# efi-shield.net
KiCad netlist of a schematic drawn in EAGLE
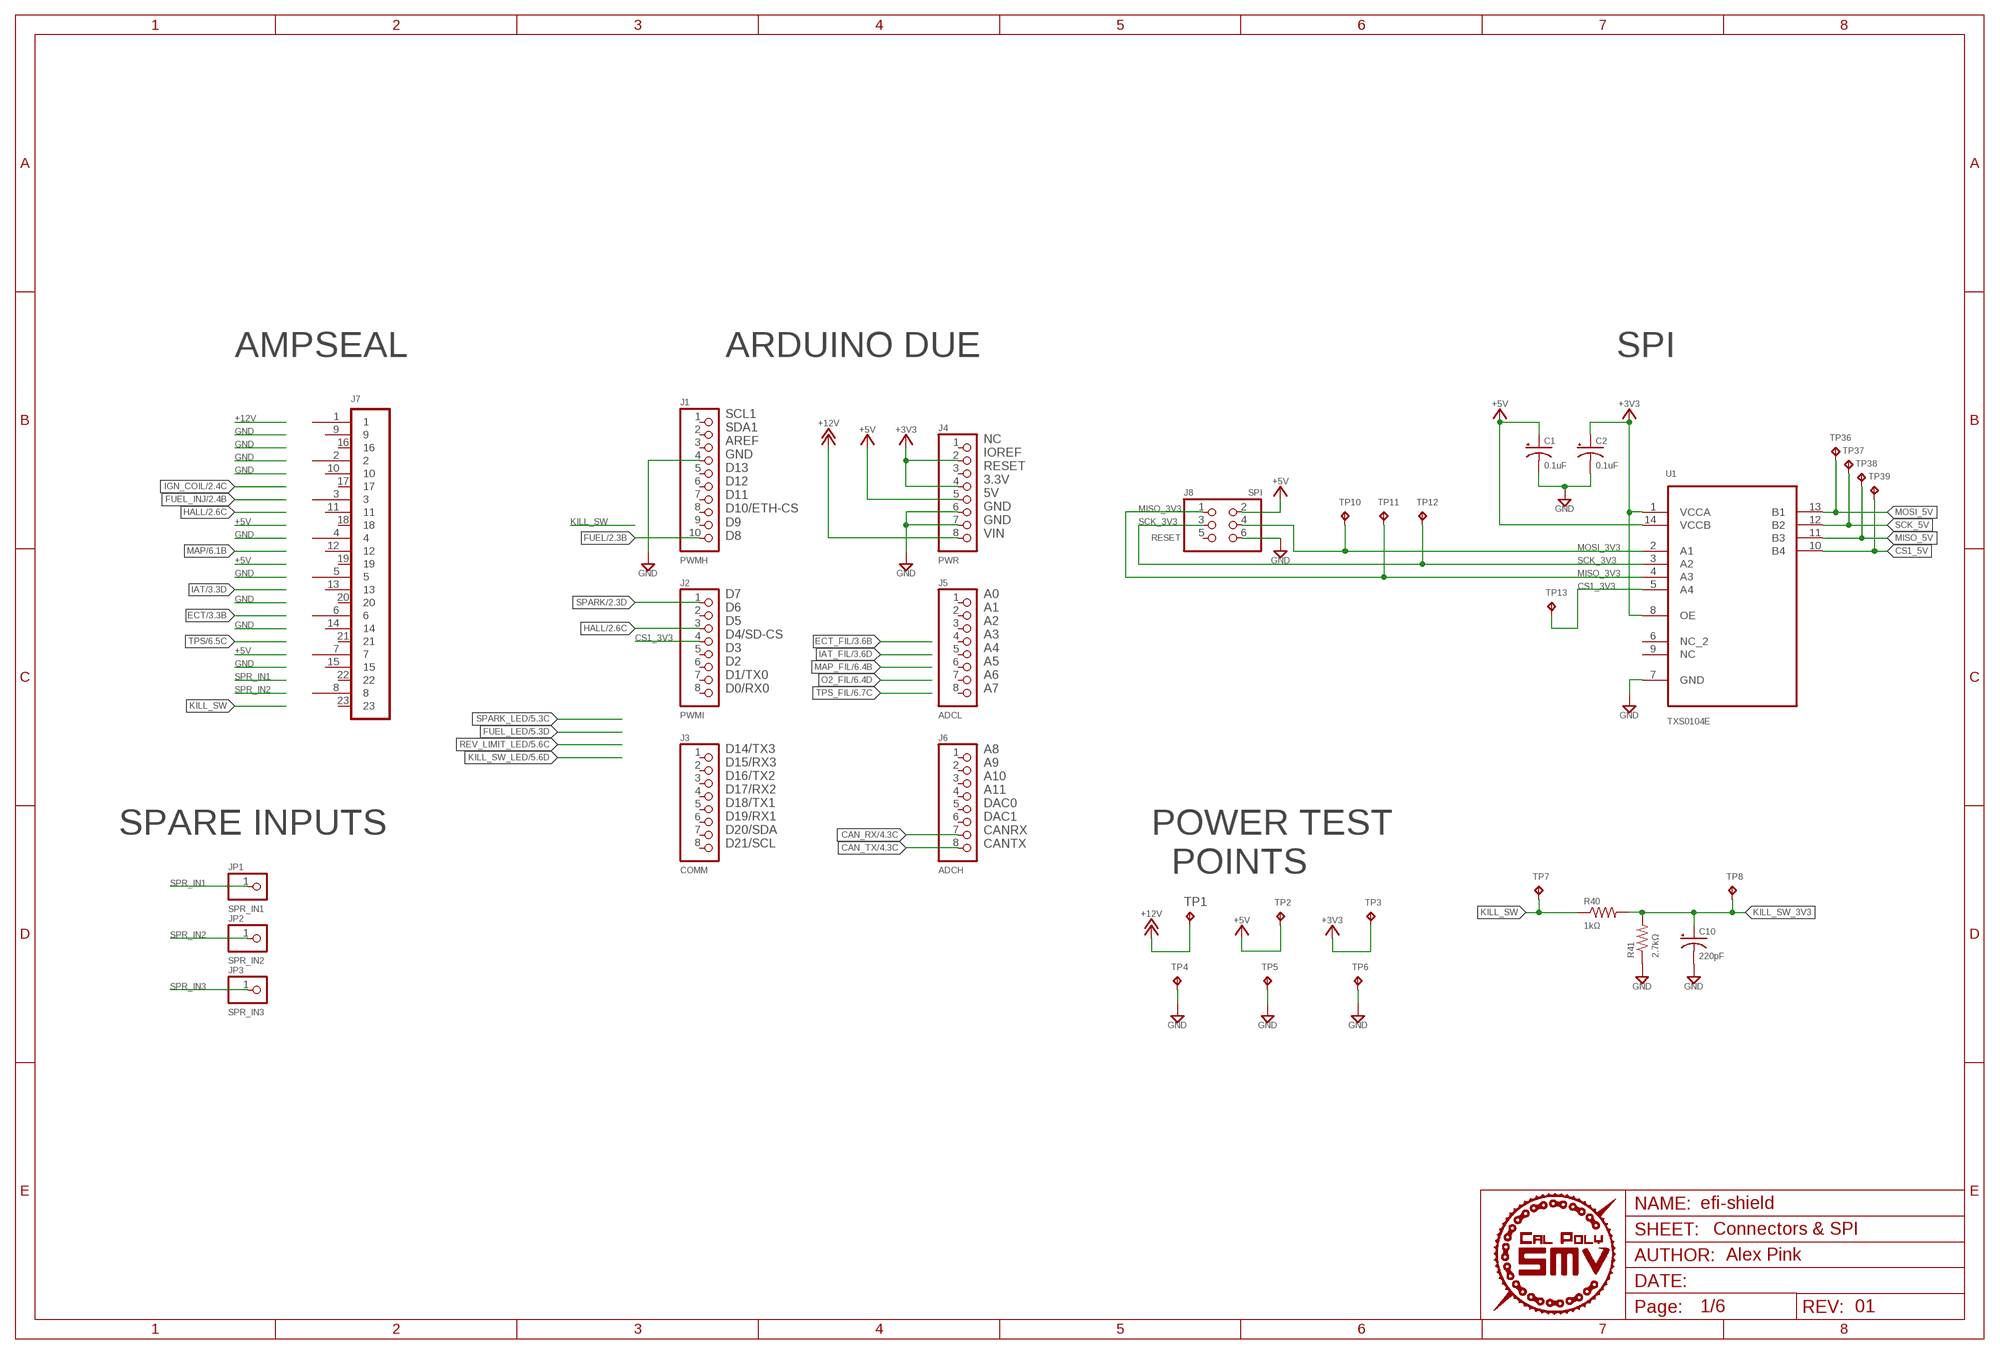
[diagram p0: schematic, sheet 1]
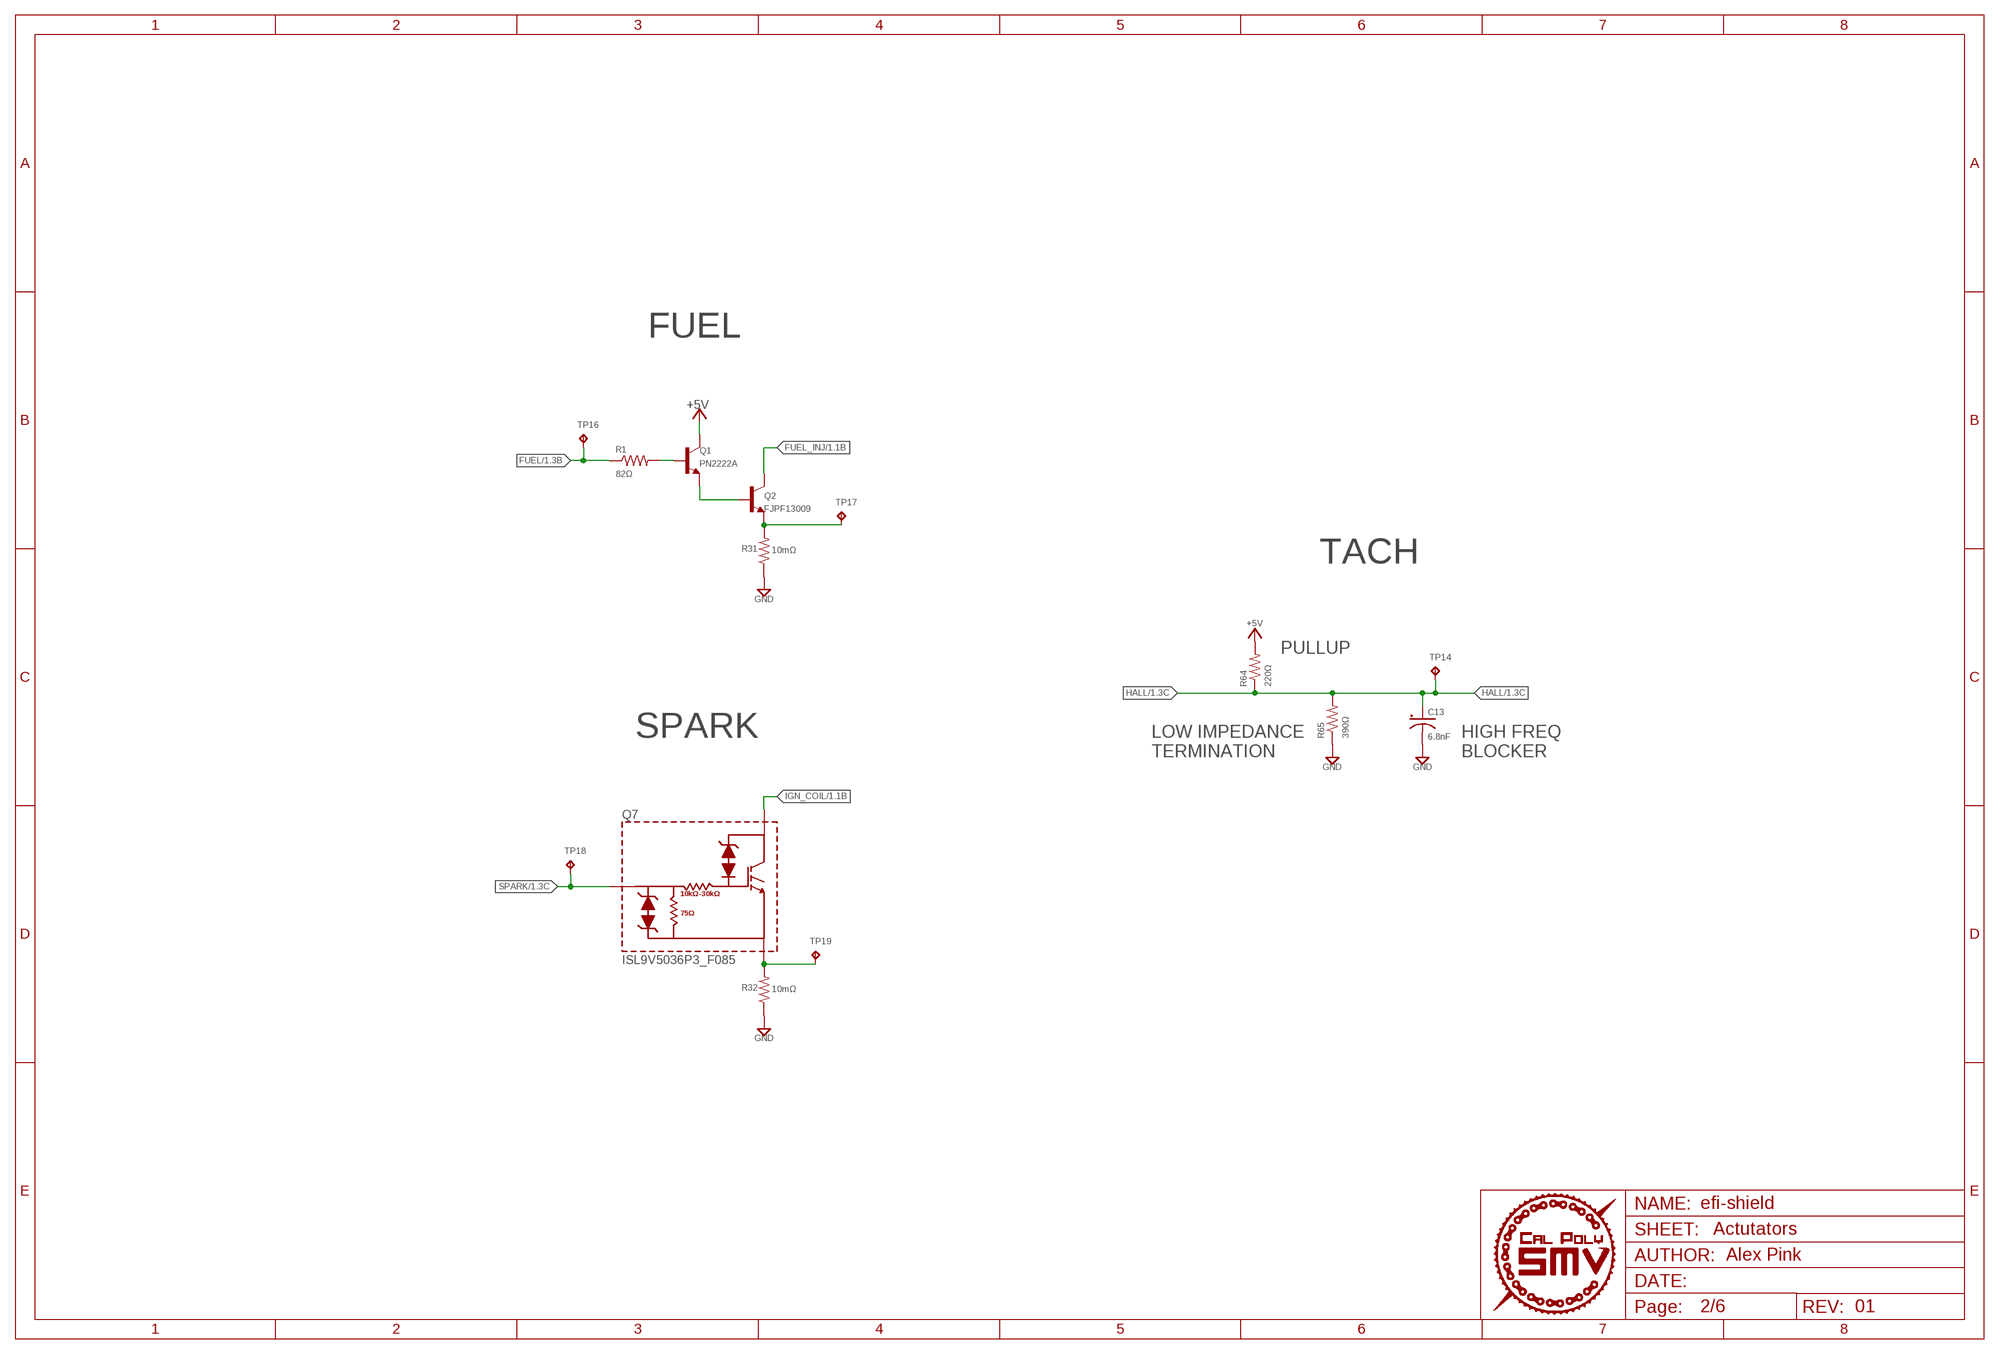
[diagram p1: schematic, sheet 2]
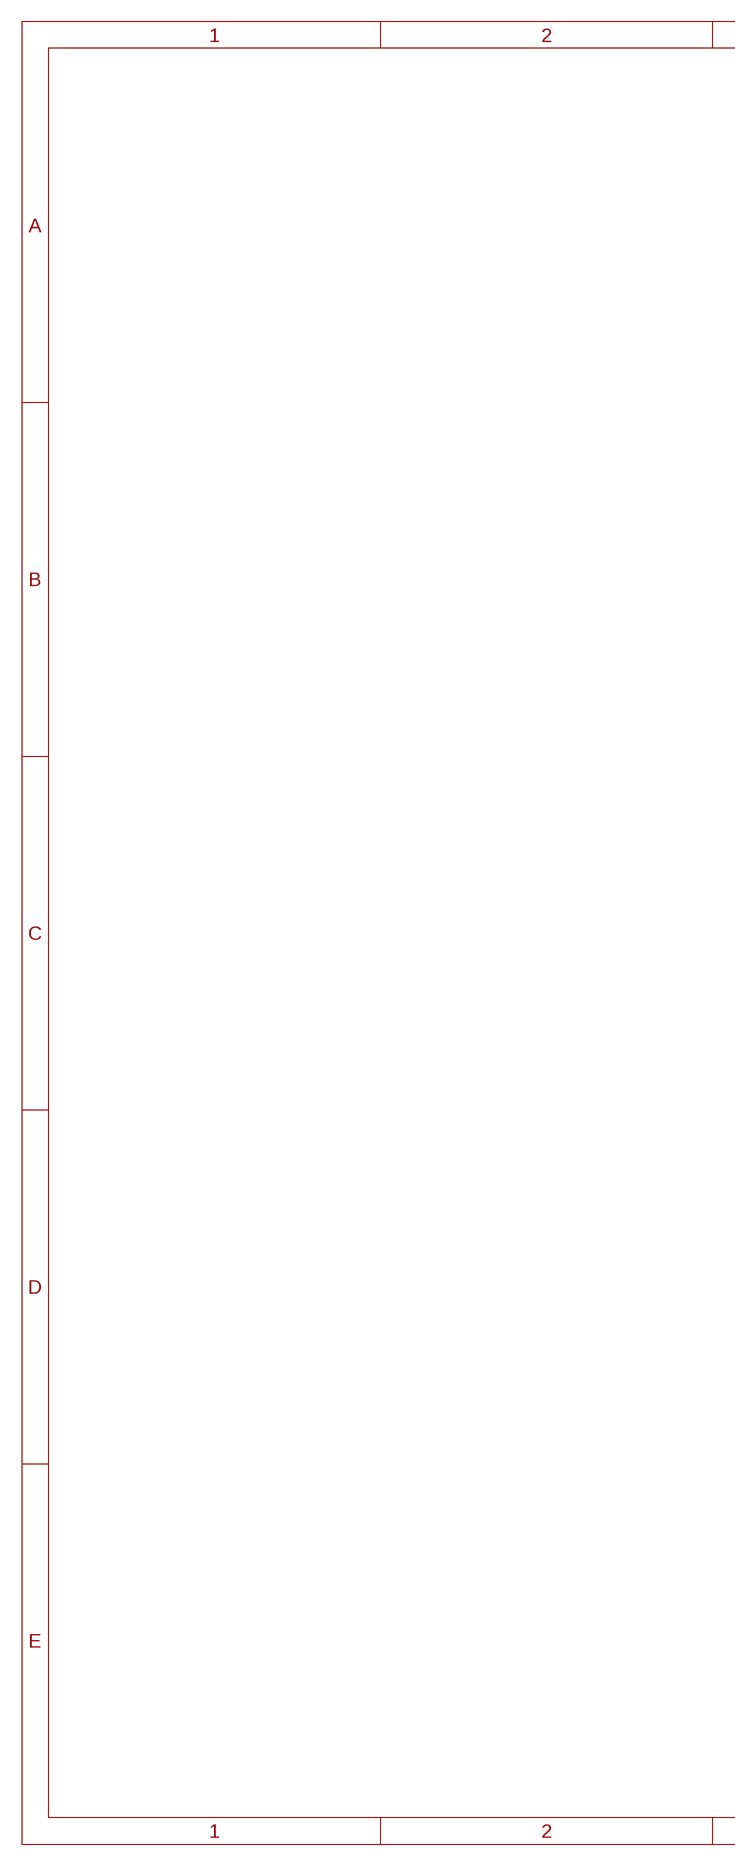
[diagram p2: schematic, sheet 3, part 1 of 2]
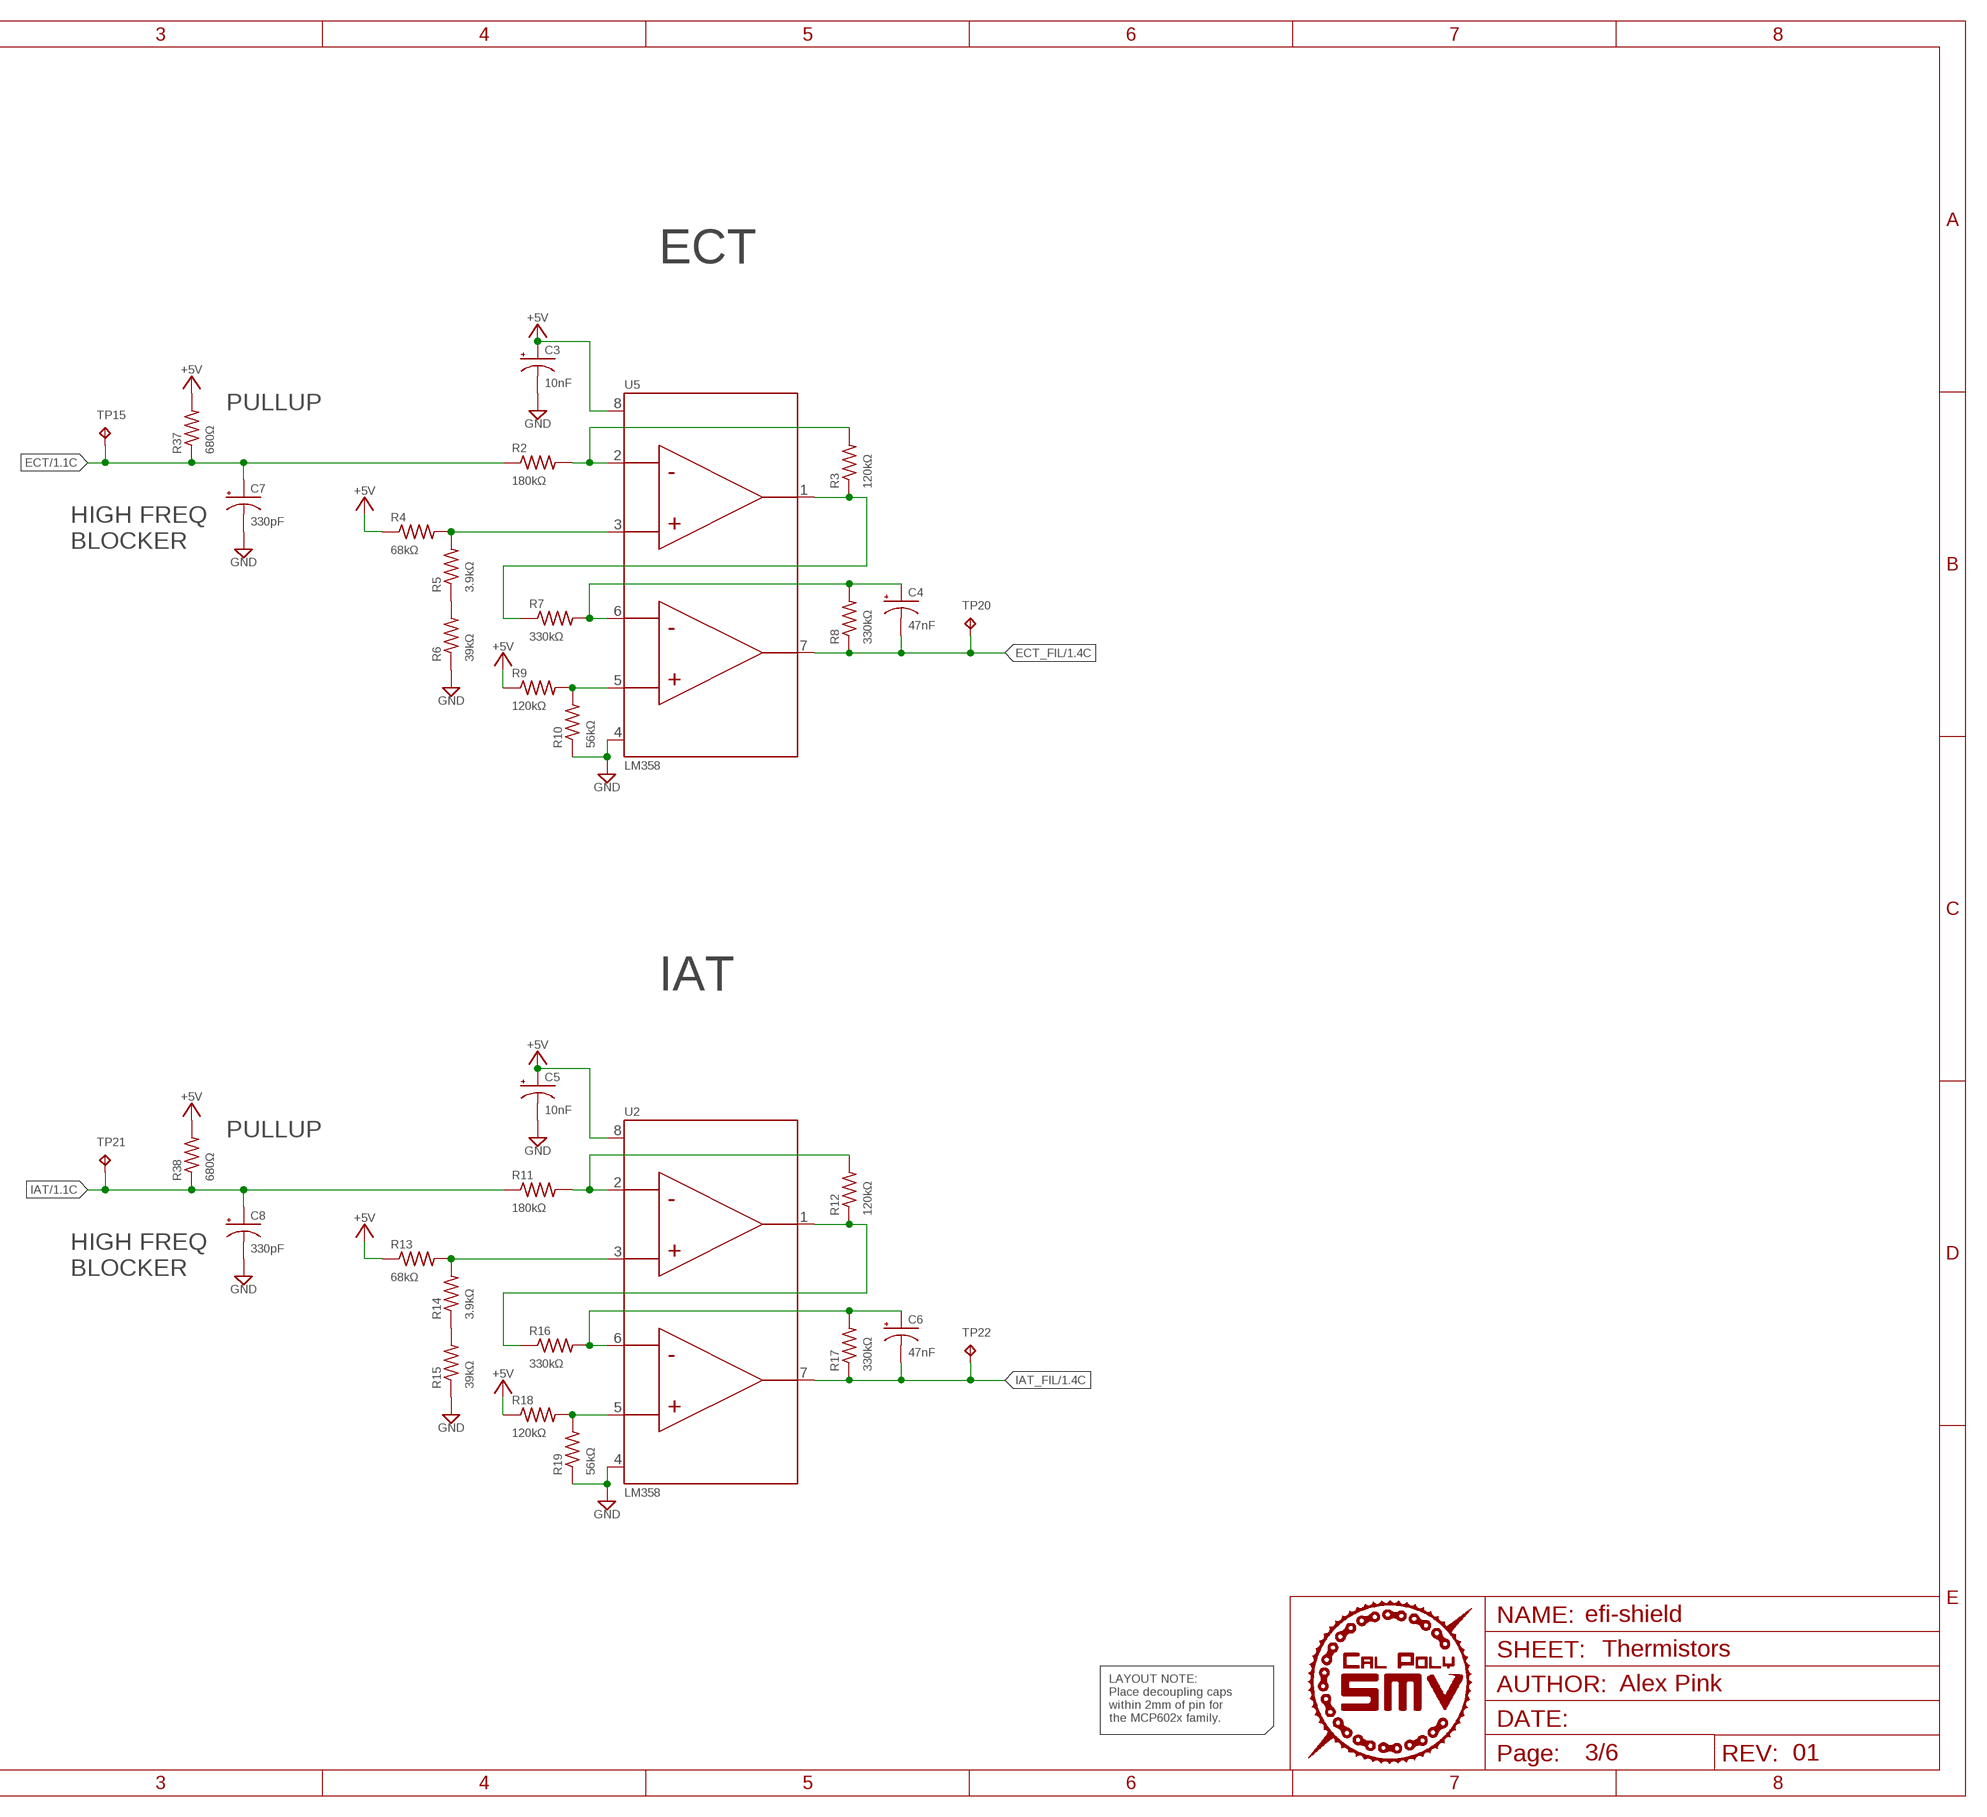
[diagram p3: schematic, sheet 3, part 2 of 2]
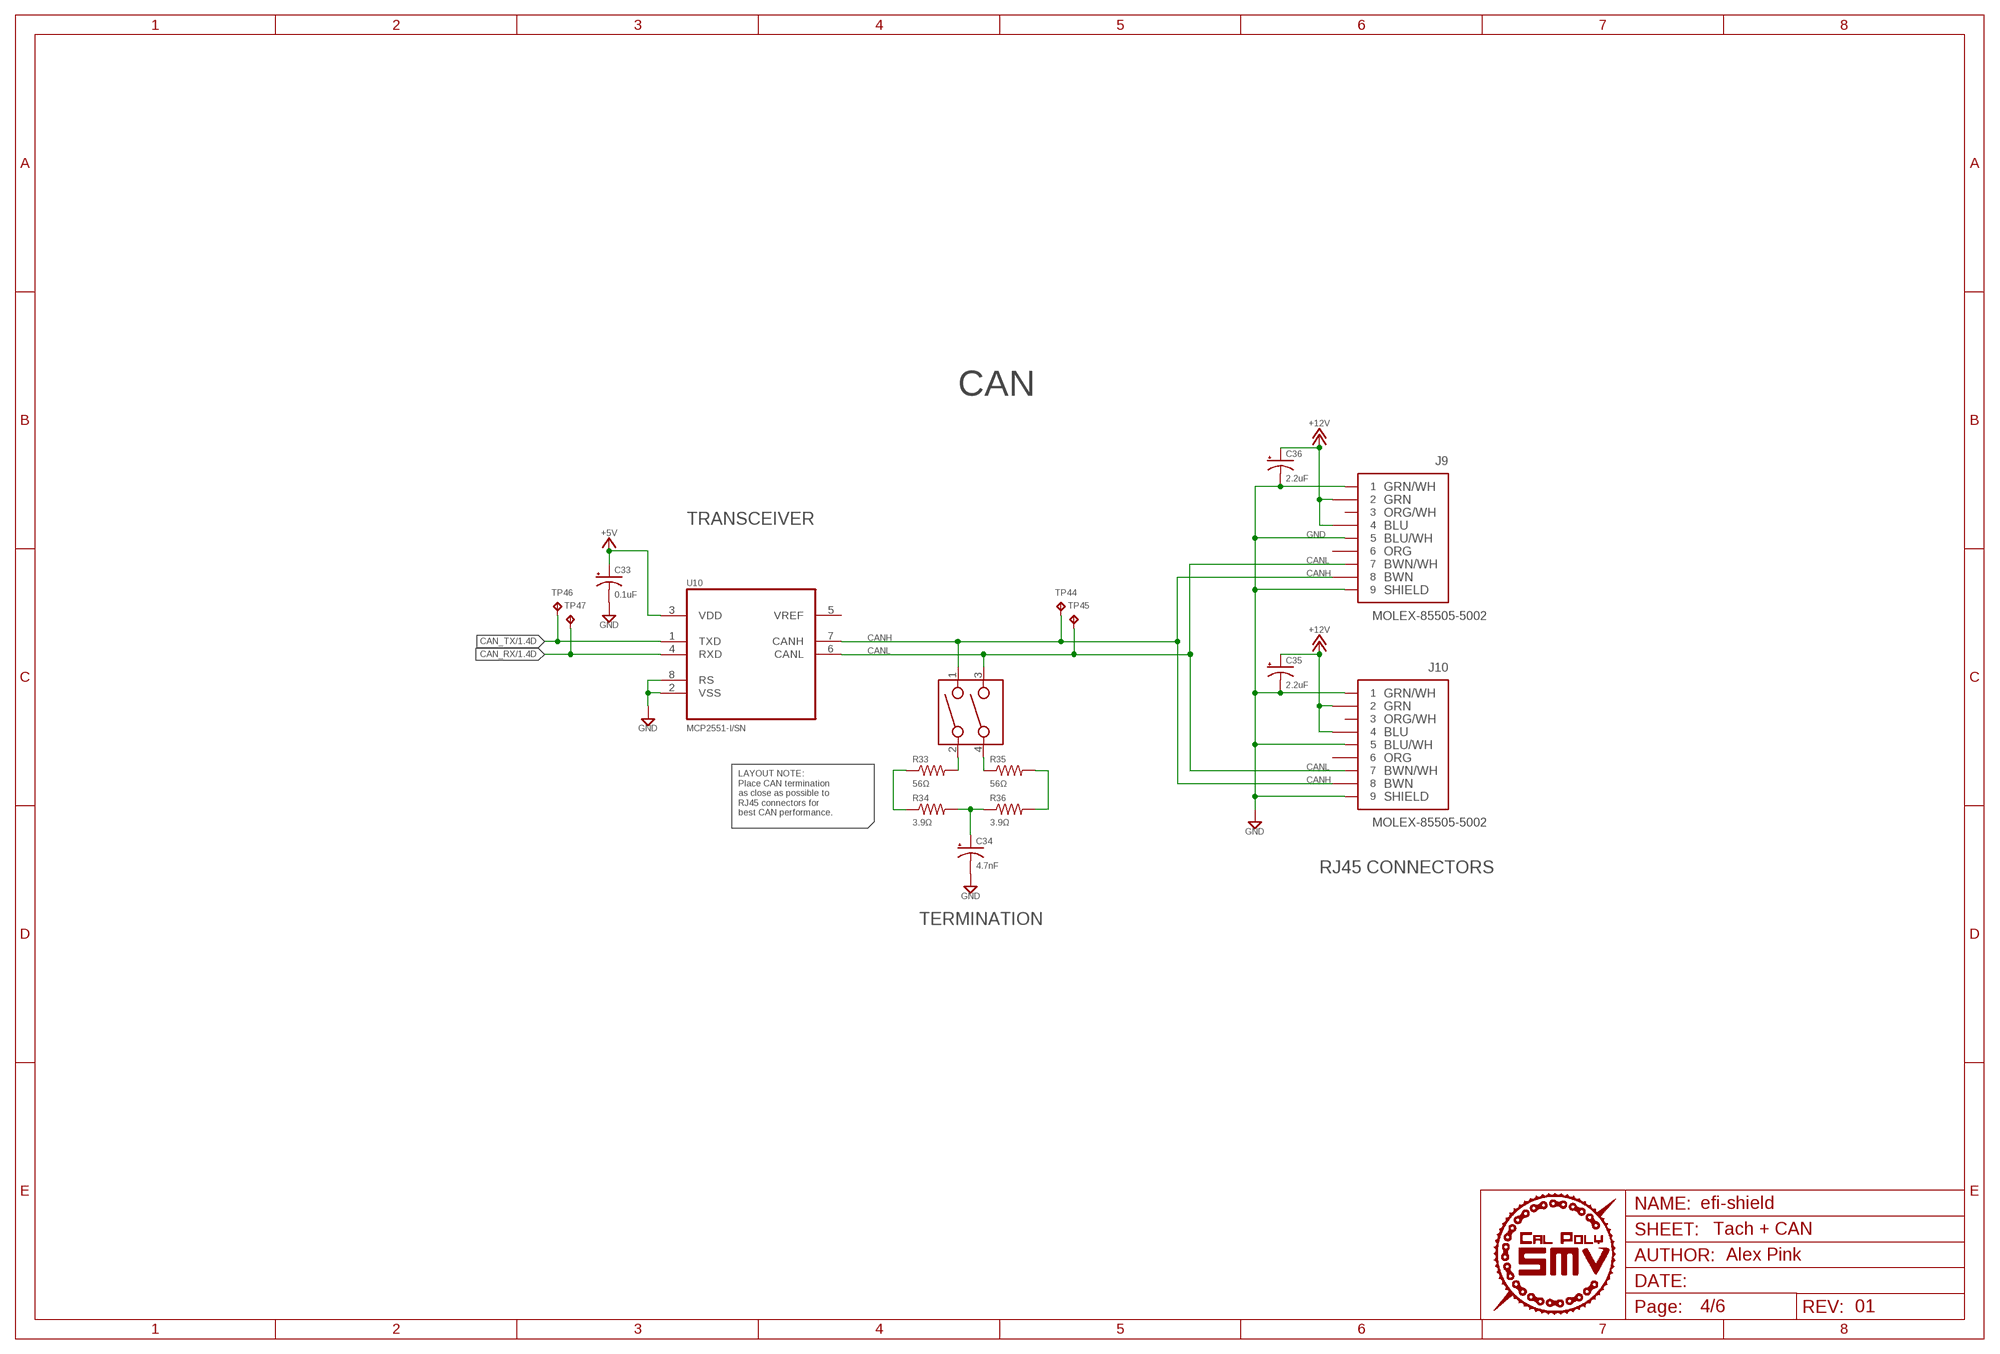
[diagram p4: schematic, sheet 4]
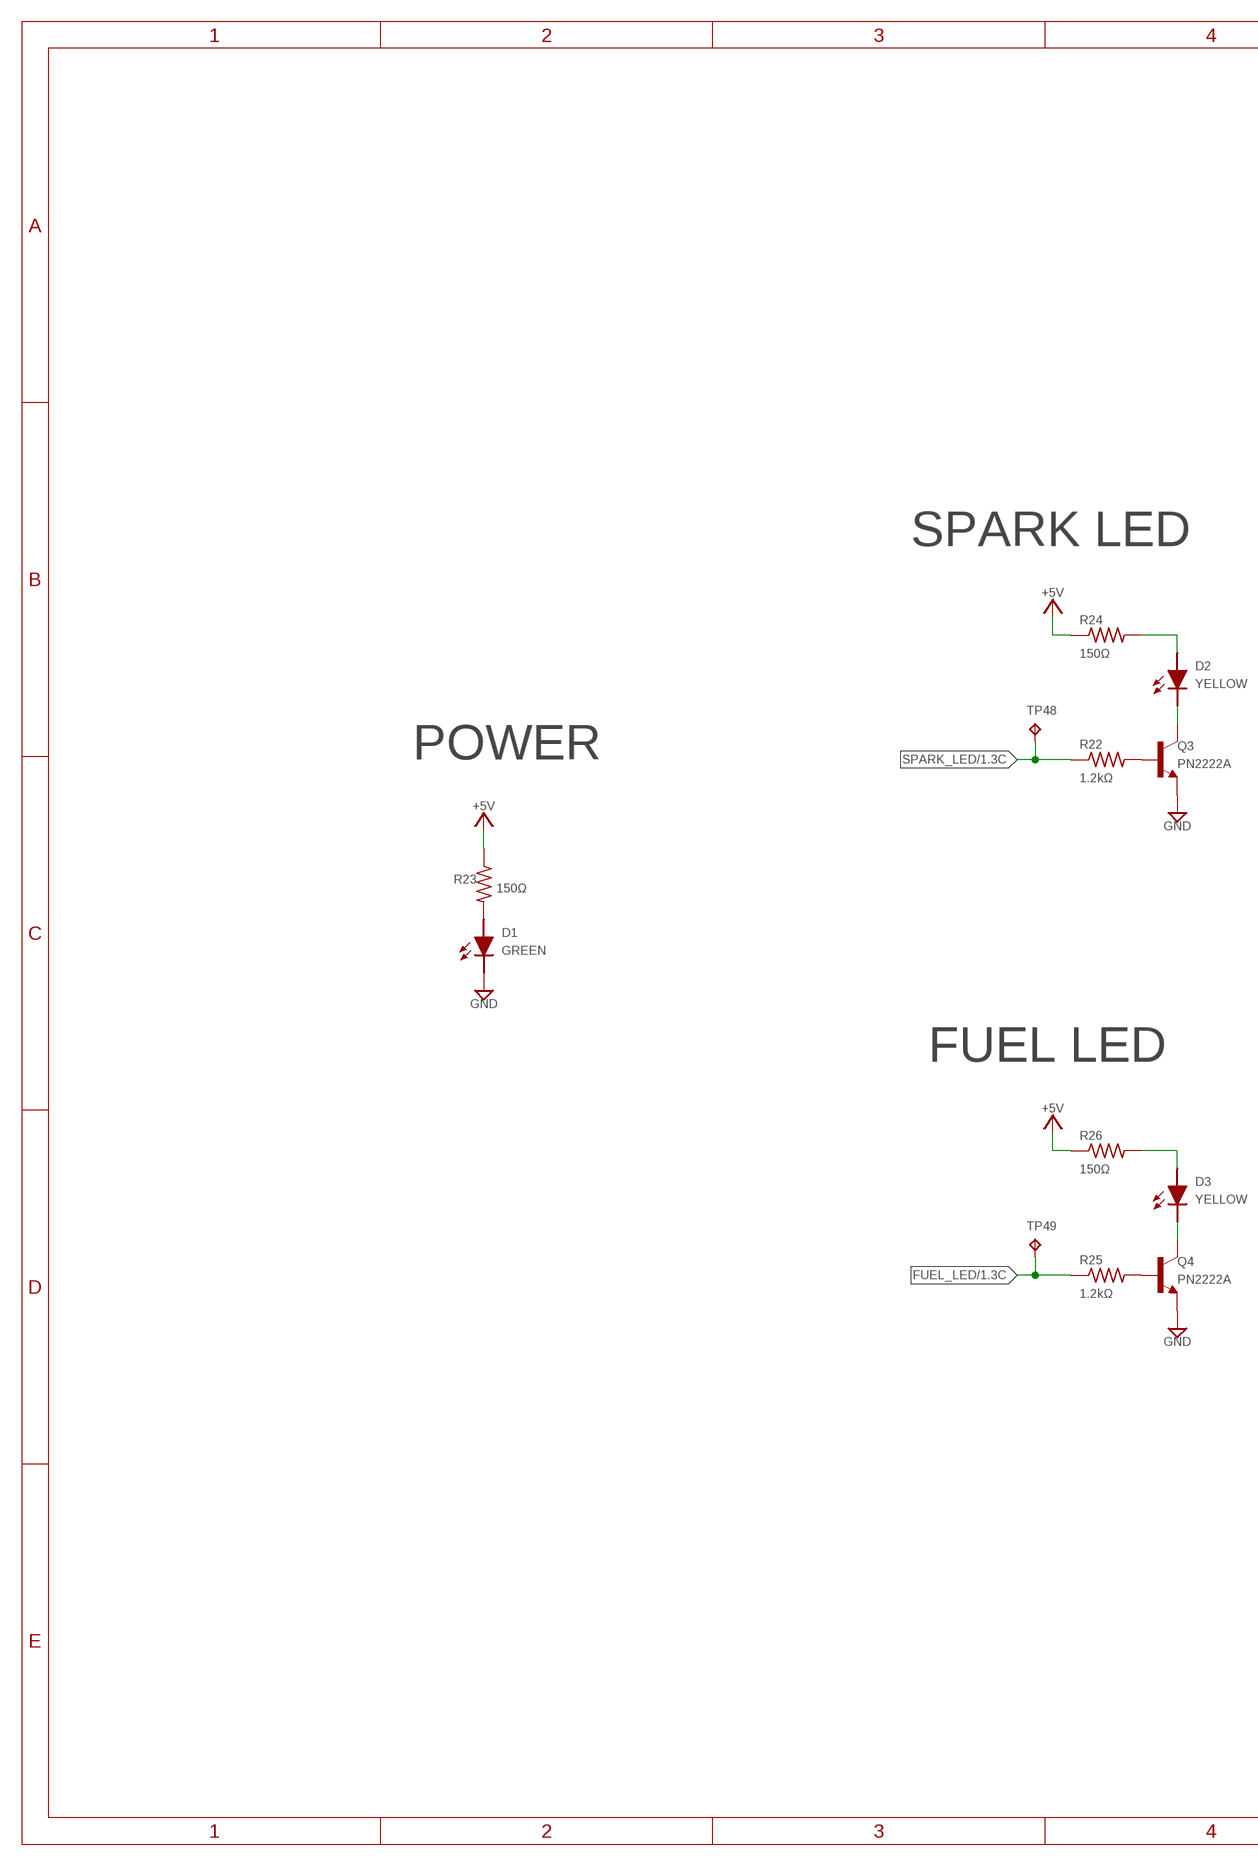
[diagram p5: schematic, sheet 5, part 1 of 2]
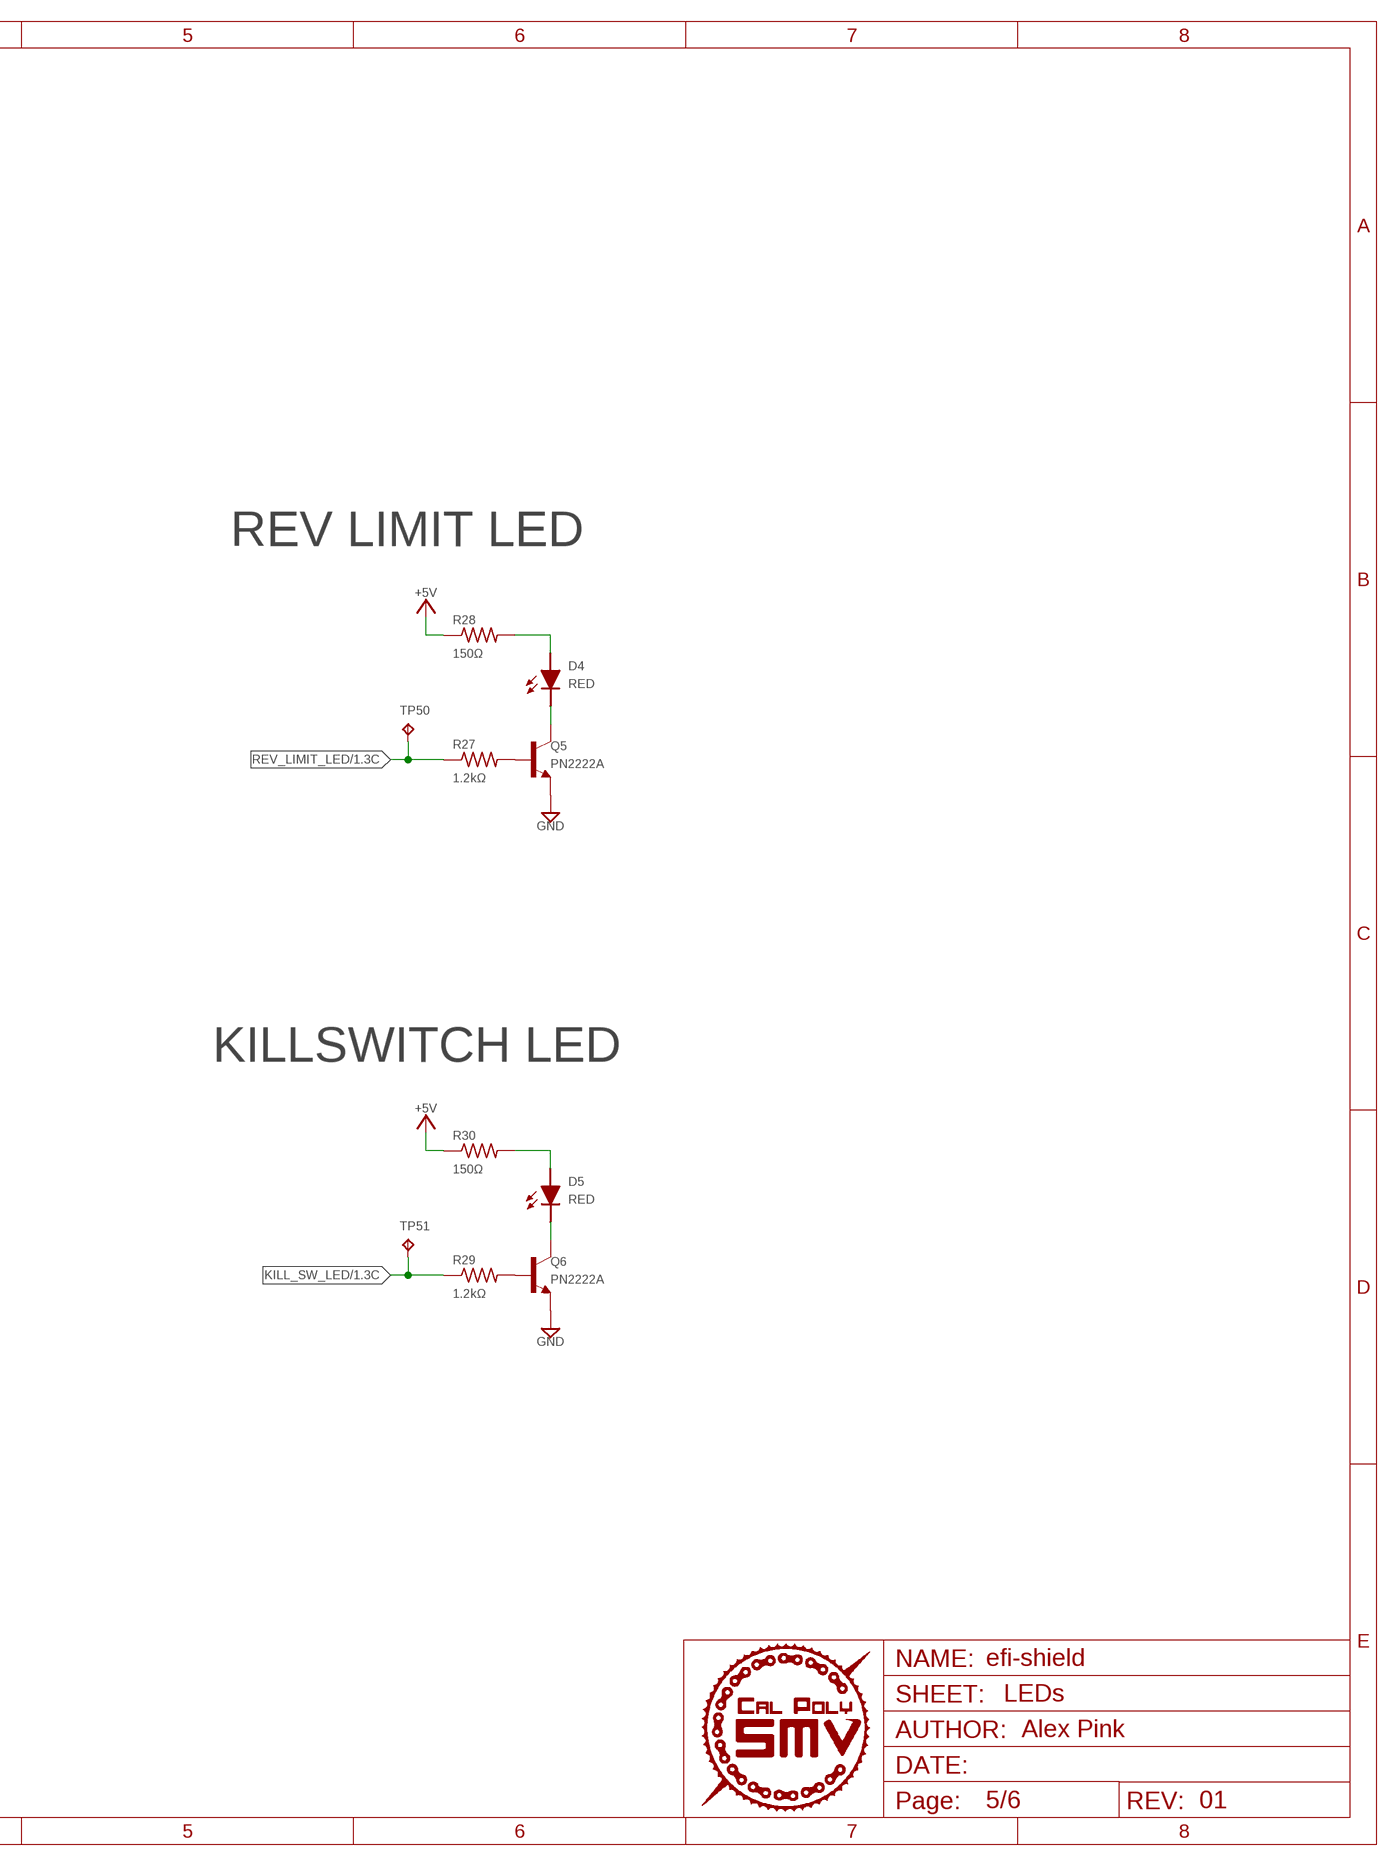
[diagram p6: schematic, sheet 5, part 2 of 2]
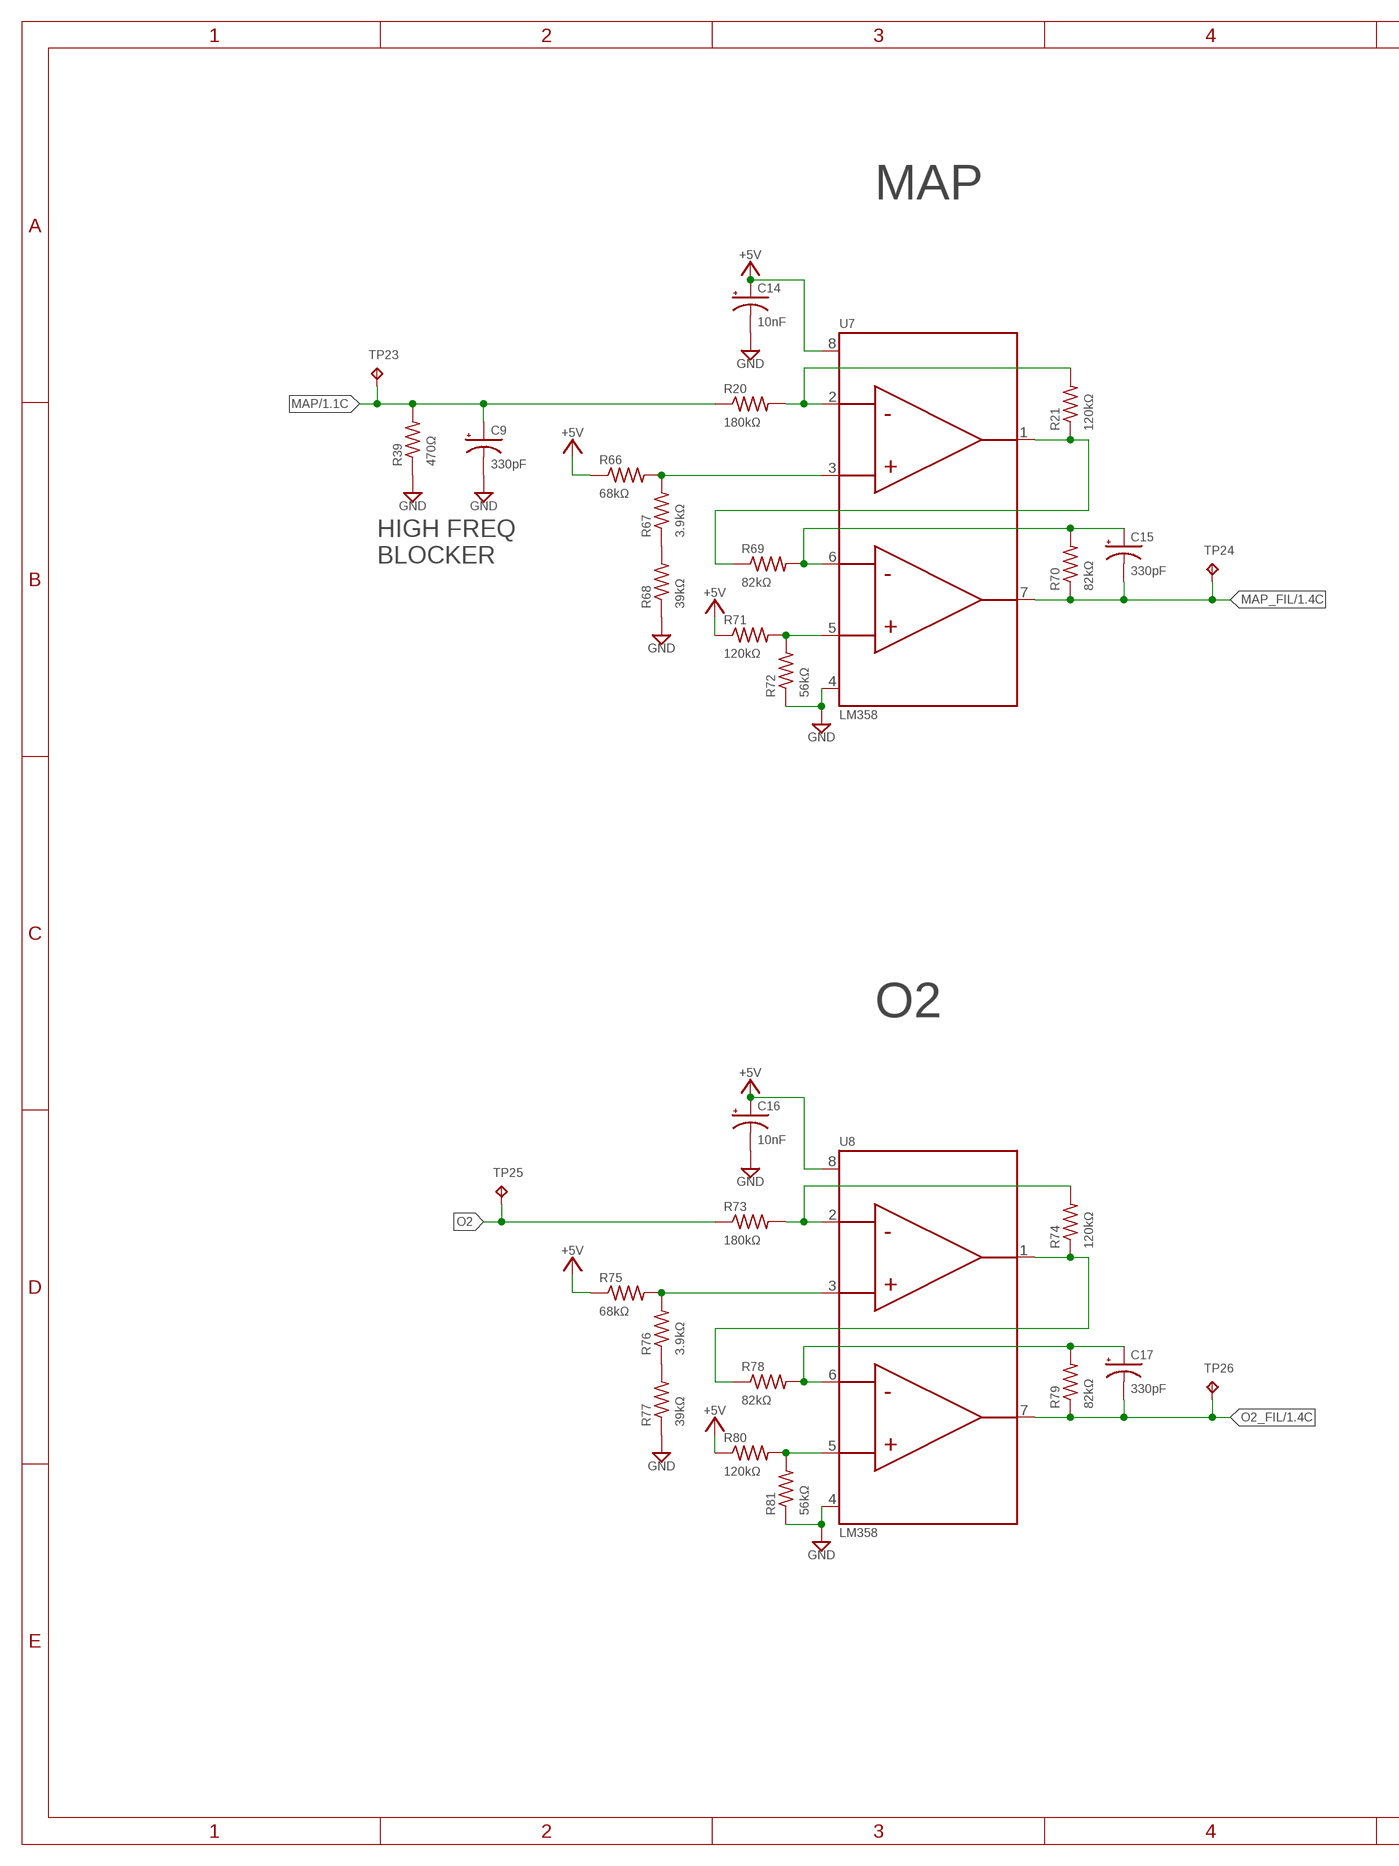
[diagram p7: schematic, sheet 6, part 1 of 2]
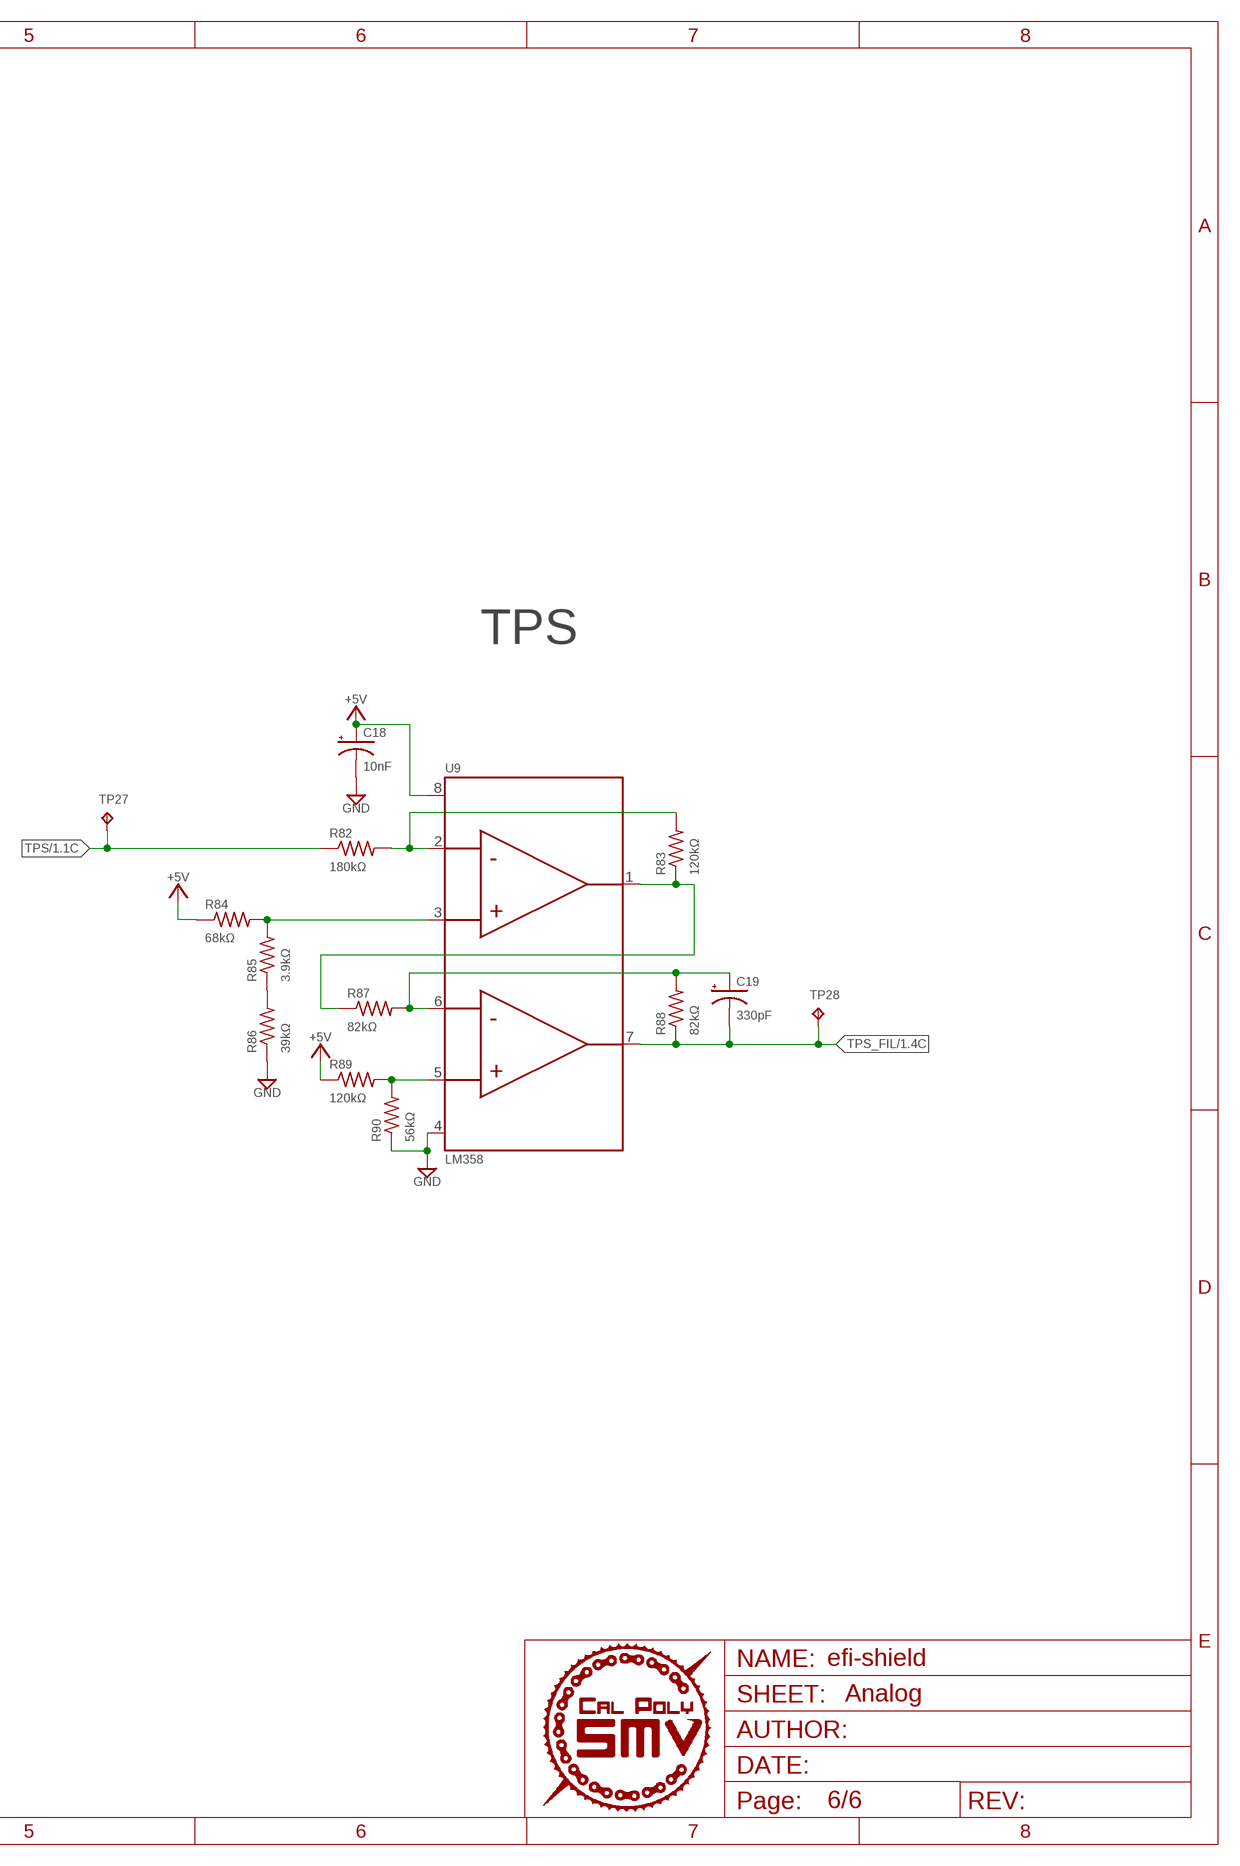
[diagram p8: schematic, sheet 6, part 2 of 2]

(export (version "E")
  (design (tool "Eeschema 10.0.6"))
  (components
    (comp (ref "C3")
      (value "10nF")
      (footprint "eagle-import:C050-025X075")
      (fields (field (name "MANUFACTURER") "joe Knows Electronics"))
      (libsource (lib "eagle-import") (part "CAP-JKE"))
    )
    (comp (ref "C4")
      (value "47nF")
      (footprint "eagle-import:C050-025X075")
      (fields (field (name "MANUFACTURER") "joe Knows Electronics"))
      (libsource (lib "eagle-import") (part "CAP-JKE"))
    )
    (comp (ref "C5")
      (value "10nF")
      (footprint "eagle-import:C050-025X075")
      (fields (field (name "MANUFACTURER") "joe Knows Electronics"))
      (libsource (lib "eagle-import") (part "CAP-JKE"))
    )
    (comp (ref "C6")
      (value "47nF")
      (footprint "eagle-import:C050-025X075")
      (fields (field (name "MANUFACTURER") "joe Knows Electronics"))
      (libsource (lib "eagle-import") (part "CAP-JKE"))
    )
    (comp (ref "C7")
      (value "330pF")
      (footprint "eagle-import:C050-025X075")
      (fields (field (name "MANUFACTURER") "joe Knows Electronics"))
      (libsource (lib "eagle-import") (part "CAP-JKE"))
    )
    (comp (ref "C8")
      (value "330pF")
      (footprint "eagle-import:C050-025X075")
      (fields (field (name "MANUFACTURER") "joe Knows Electronics"))
      (libsource (lib "eagle-import") (part "CAP-JKE"))
    )
    (comp (ref "R2")
      (value "180kΩ")
      (footprint "eagle-import:0207_7")
      (fields (field (name "MANUFACTURER") "Joe Knows Electronics"))
      (libsource (lib "eagle-import") (part "RES-JKE"))
    )
    (comp (ref "R3")
      (value "120kΩ")
      (footprint "eagle-import:0207_7")
      (fields (field (name "MANUFACTURER") "Joe Knows Electronics"))
      (libsource (lib "eagle-import") (part "RES-JKE"))
    )
    (comp (ref "R4")
      (value "68kΩ")
      (footprint "eagle-import:0207_7")
      (fields (field (name "MANUFACTURER") "Joe Knows Electronics"))
      (libsource (lib "eagle-import") (part "RES-JKE"))
    )
    (comp (ref "R5")
      (value "3.9kΩ")
      (footprint "eagle-import:0207_7")
      (fields (field (name "MANUFACTURER") "Joe Knows Electronics"))
      (libsource (lib "eagle-import") (part "RES-JKE"))
    )
    (comp (ref "R6")
      (value "39kΩ")
      (footprint "eagle-import:0207_7")
      (fields (field (name "MANUFACTURER") "Joe Knows Electronics"))
      (libsource (lib "eagle-import") (part "RES-JKE"))
    )
    (comp (ref "R7")
      (value "330kΩ")
      (footprint "eagle-import:0207_7")
      (fields (field (name "MANUFACTURER") "Joe Knows Electronics"))
      (libsource (lib "eagle-import") (part "RES-JKE"))
    )
    (comp (ref "R8")
      (value "330kΩ")
      (footprint "eagle-import:0207_7")
      (fields (field (name "MANUFACTURER") "Joe Knows Electronics"))
      (libsource (lib "eagle-import") (part "RES-JKE"))
    )
    (comp (ref "R9")
      (value "120kΩ")
      (footprint "eagle-import:0207_7")
      (fields (field (name "MANUFACTURER") "Joe Knows Electronics"))
      (libsource (lib "eagle-import") (part "RES-JKE"))
    )
    (comp (ref "R10")
      (value "56kΩ")
      (footprint "eagle-import:0207_7")
      (fields (field (name "MANUFACTURER") "Joe Knows Electronics"))
      (libsource (lib "eagle-import") (part "RES-JKE"))
    )
    (comp (ref "R11")
      (value "180kΩ")
      (footprint "eagle-import:0207_7")
      (fields (field (name "MANUFACTURER") "Joe Knows Electronics"))
      (libsource (lib "eagle-import") (part "RES-JKE"))
    )
    (comp (ref "R12")
      (value "120kΩ")
      (footprint "eagle-import:0207_7")
      (fields (field (name "MANUFACTURER") "Joe Knows Electronics"))
      (libsource (lib "eagle-import") (part "RES-JKE"))
    )
    (comp (ref "R13")
      (value "68kΩ")
      (footprint "eagle-import:0207_7")
      (fields (field (name "MANUFACTURER") "Joe Knows Electronics"))
      (libsource (lib "eagle-import") (part "RES-JKE"))
    )
    (comp (ref "R14")
      (value "3.9kΩ")
      (footprint "eagle-import:0207_7")
      (fields (field (name "MANUFACTURER") "Joe Knows Electronics"))
      (libsource (lib "eagle-import") (part "RES-JKE"))
    )
    (comp (ref "R15")
      (value "39kΩ")
      (footprint "eagle-import:0207_7")
      (fields (field (name "MANUFACTURER") "Joe Knows Electronics"))
      (libsource (lib "eagle-import") (part "RES-JKE"))
    )
    (comp (ref "R16")
      (value "330kΩ")
      (footprint "eagle-import:0207_7")
      (fields (field (name "MANUFACTURER") "Joe Knows Electronics"))
      (libsource (lib "eagle-import") (part "RES-JKE"))
    )
    (comp (ref "R17")
      (value "330kΩ")
      (footprint "eagle-import:0207_7")
      (fields (field (name "MANUFACTURER") "Joe Knows Electronics"))
      (libsource (lib "eagle-import") (part "RES-JKE"))
    )
    (comp (ref "R18")
      (value "120kΩ")
      (footprint "eagle-import:0207_7")
      (fields (field (name "MANUFACTURER") "Joe Knows Electronics"))
      (libsource (lib "eagle-import") (part "RES-JKE"))
    )
    (comp (ref "R19")
      (value "56kΩ")
      (footprint "eagle-import:0207_7")
      (fields (field (name "MANUFACTURER") "Joe Knows Electronics"))
      (libsource (lib "eagle-import") (part "RES-JKE"))
    )
    (comp (ref "R37")
      (value "680Ω")
      (footprint "eagle-import:0207_7")
      (fields (field (name "MANUFACTURER") "Joe Knows Electronics"))
      (libsource (lib "eagle-import") (part "RES-JKE"))
    )
    (comp (ref "R38")
      (value "680Ω")
      (footprint "eagle-import:0207_7")
      (fields (field (name "MANUFACTURER") "Joe Knows Electronics"))
      (libsource (lib "eagle-import") (part "RES-JKE"))
    )
    (comp (ref "TP15")
      (value "ECT")
      (footprint "eagle-import:TP-P1-20")
      (libsource (lib "eagle-import") (part "TEST-POINT"))
    )
    (comp (ref "TP20")
      (value "ECT_FIL")
      (footprint "eagle-import:TP-P1-20")
      (libsource (lib "eagle-import") (part "TEST-POINT"))
    )
    (comp (ref "TP21")
      (value "IAT")
      (footprint "eagle-import:TP-P1-20")
      (libsource (lib "eagle-import") (part "TEST-POINT"))
    )
    (comp (ref "TP22")
      (value "IAT_FIL")
      (footprint "eagle-import:TP-P1-20")
      (libsource (lib "eagle-import") (part "TEST-POINT"))
    )
    (comp (ref "U2")
      (value "LM358")
      (footprint "eagle-import:SOP08")
      (fields (field (name "MANUFACTURER") "Texas Instruments"))
      (libsource (lib "eagle-import") (part "LM358"))
    )
    (comp (ref "U5")
      (value "LM358")
      (footprint "eagle-import:SOP08")
      (fields (field (name "MANUFACTURER") "Texas Instruments"))
      (libsource (lib "eagle-import") (part "LM358"))
    )
    (comp (ref "C1")
      (value "0.1uF")
      (footprint "eagle-import:C050-025X075")
      (fields (field (name "MANUFACTURER") "joe Knows Electronics"))
      (libsource (lib "eagle-import") (part "CAP-JKE"))
    )
    (comp (ref "C2")
      (value "0.1uF")
      (footprint "eagle-import:C050-025X075")
      (fields (field (name "MANUFACTURER") "joe Knows Electronics"))
      (libsource (lib "eagle-import") (part "CAP-JKE"))
    )
    (comp (ref "C10")
      (value "220pF")
      (footprint "eagle-import:C050-025X075")
      (fields (field (name "MANUFACTURER") "joe Knows Electronics"))
      (libsource (lib "eagle-import") (part "CAP-JKE"))
    )
    (comp (ref "J1")
      (value "PWMH")
      (footprint "eagle-import:1X10")
      (fields (field (name "MANUFACTURER") "Joe Knows Electronics"))
      (libsource (lib "eagle-import") (part "PINHD-1X10"))
    )
    (comp (ref "J2")
      (value "PWMI")
      (footprint "eagle-import:1X08")
      (fields (field (name "MANUFACTURER") "Joe Knows Electronics"))
      (libsource (lib "eagle-import") (part "PINHD-1X8"))
    )
    (comp (ref "J3")
      (value "COMM")
      (footprint "eagle-import:1X08")
      (fields (field (name "MANUFACTURER") "Joe Knows Electronics"))
      (libsource (lib "eagle-import") (part "PINHD-1X8"))
    )
    (comp (ref "J4")
      (value "PWR")
      (footprint "eagle-import:1X08")
      (fields (field (name "MANUFACTURER") "Joe Knows Electronics"))
      (libsource (lib "eagle-import") (part "PINHD-1X8"))
    )
    (comp (ref "J5")
      (value "ADCL")
      (footprint "eagle-import:1X08")
      (fields (field (name "MANUFACTURER") "Joe Knows Electronics"))
      (libsource (lib "eagle-import") (part "PINHD-1X8"))
    )
    (comp (ref "J6")
      (value "ADCH")
      (footprint "eagle-import:1X08")
      (fields (field (name "MANUFACTURER") "Joe Knows Electronics"))
      (libsource (lib "eagle-import") (part "PINHD-1X8"))
    )
    (comp (ref "J7")
      (value "AMPSEAL-23POS-HEADER")
      (footprint "eagle-import:AMPSEAL-HEADER-23POS-RA")
      (fields (field (name "MANUFACTURER") "TE Connectivity"))
      (libsource (lib "eagle-import") (part "AMPSEAL-23POS-HEADER"))
    )
    (comp (ref "J8")
      (value "SPI")
      (footprint "eagle-import:2X03")
      (fields (field (name "MANUFACTURER") "Joe Knows Electronics"))
      (libsource (lib "eagle-import") (part "PINHD-2X3"))
    )
    (comp (ref "JP1")
      (value "SPR_IN1")
      (footprint "eagle-import:1X01")
      (fields (field (name "MANUFACTURER") "Joe Knows Electronics"))
      (libsource (lib "eagle-import") (part "PINHD-1X1"))
    )
    (comp (ref "JP2")
      (value "SPR_IN2")
      (footprint "eagle-import:1X01")
      (fields (field (name "MANUFACTURER") "Joe Knows Electronics"))
      (libsource (lib "eagle-import") (part "PINHD-1X1"))
    )
    (comp (ref "JP3")
      (value "SPR_IN3")
      (footprint "eagle-import:1X01")
      (fields (field (name "MANUFACTURER") "Joe Knows Electronics"))
      (libsource (lib "eagle-import") (part "PINHD-1X1"))
    )
    (comp (ref "R40")
      (value "1kΩ")
      (footprint "eagle-import:0207_7")
      (fields (field (name "MANUFACTURER") "Joe Knows Electronics"))
      (libsource (lib "eagle-import") (part "RES-JKE"))
    )
    (comp (ref "R41")
      (value "2.7kΩ")
      (footprint "eagle-import:0207_7")
      (fields (field (name "MANUFACTURER") "Joe Knows Electronics"))
      (libsource (lib "eagle-import") (part "RES-JKE"))
    )
    (comp (ref "TP1")
      (value "+12V")
      (footprint "eagle-import:TP-P1-20")
      (libsource (lib "eagle-import") (part "TEST-POINT"))
    )
    (comp (ref "TP2")
      (value "+5V")
      (footprint "eagle-import:TP-P1-20")
      (libsource (lib "eagle-import") (part "TEST-POINT"))
    )
    (comp (ref "TP3")
      (value "+3V3")
      (footprint "eagle-import:TP-P1-20")
      (libsource (lib "eagle-import") (part "TEST-POINT"))
    )
    (comp (ref "TP4")
      (value "GND")
      (footprint "eagle-import:TP-P1-20")
      (libsource (lib "eagle-import") (part "TEST-POINT"))
    )
    (comp (ref "TP5")
      (value "GND")
      (footprint "eagle-import:TP-P1-20")
      (libsource (lib "eagle-import") (part "TEST-POINT"))
    )
    (comp (ref "TP6")
      (value "GND")
      (footprint "eagle-import:TP-P1-20")
      (libsource (lib "eagle-import") (part "TEST-POINT"))
    )
    (comp (ref "TP7")
      (value "KILL_SW")
      (footprint "eagle-import:TP-P1-20")
      (libsource (lib "eagle-import") (part "TEST-POINT"))
    )
    (comp (ref "TP8")
      (value "KILL_SW_3V3")
      (footprint "eagle-import:TP-P1-20")
      (libsource (lib "eagle-import") (part "TEST-POINT"))
    )
    (comp (ref "TP10")
      (value "MOSI_3V3")
      (footprint "eagle-import:TP-P1-20")
      (libsource (lib "eagle-import") (part "TEST-POINT"))
    )
    (comp (ref "TP11")
      (value "MISO_3V3")
      (footprint "eagle-import:TP-P1-20")
      (libsource (lib "eagle-import") (part "TEST-POINT"))
    )
    (comp (ref "TP12")
      (value "SCK_3V3")
      (footprint "eagle-import:TP-P1-20")
      (libsource (lib "eagle-import") (part "TEST-POINT"))
    )
    (comp (ref "TP13")
      (value "CS1_3V3")
      (footprint "eagle-import:TP-P1-20")
      (libsource (lib "eagle-import") (part "TEST-POINT"))
    )
    (comp (ref "TP36")
      (value "MOSI_5V")
      (footprint "eagle-import:TP-P1-20")
      (libsource (lib "eagle-import") (part "TEST-POINT"))
    )
    (comp (ref "TP37")
      (value "SCK_5V")
      (footprint "eagle-import:TP-P1-20")
      (libsource (lib "eagle-import") (part "TEST-POINT"))
    )
    (comp (ref "TP38")
      (value "MISO_5V")
      (footprint "eagle-import:TP-P1-20")
      (libsource (lib "eagle-import") (part "TEST-POINT"))
    )
    (comp (ref "TP39")
      (value "CS1_5V")
      (footprint "eagle-import:TP-P1-20")
      (libsource (lib "eagle-import") (part "TEST-POINT"))
    )
    (comp (ref "U1")
      (value "TXS0104E")
      (footprint "eagle-import:SOIC127P600X175-14N")
      (fields (field (name "MANUFACTURER") "Texas Instruments"))
      (libsource (lib "eagle-import") (part "TXS0104ED"))
    )
    (comp (ref "C33")
      (value "0.1uF")
      (footprint "eagle-import:C050-025X075")
      (fields (field (name "MANUFACTURER") "joe Knows Electronics"))
      (libsource (lib "eagle-import") (part "CAP-JKE"))
    )
    (comp (ref "C34")
      (value "4.7nF")
      (footprint "eagle-import:C050-025X075")
      (fields (field (name "MANUFACTURER") "joe Knows Electronics"))
      (libsource (lib "eagle-import") (part "CAP-JKE"))
    )
    (comp (ref "C35")
      (value "2.2uF")
      (footprint "eagle-import:C050-025X075")
      (fields (field (name "MANUFACTURER") "joe Knows Electronics"))
      (libsource (lib "eagle-import") (part "CAP-JKE"))
    )
    (comp (ref "C36")
      (value "2.2uF")
      (footprint "eagle-import:C050-025X075")
      (fields (field (name "MANUFACTURER") "joe Knows Electronics"))
      (libsource (lib "eagle-import") (part "CAP-JKE"))
    )
    (comp (ref "J9")
      (value "MOLEX-85505-5002")
      (footprint "eagle-import:85505-5002")
      (fields (field (name "MANUFACTURER") "Molx"))
      (libsource (lib "eagle-import") (part "MOLEX-85505-5002"))
    )
    (comp (ref "J10")
      (value "MOLEX-85505-5002")
      (footprint "eagle-import:85505-5002")
      (fields (field (name "MANUFACTURER") "Molx"))
      (libsource (lib "eagle-import") (part "MOLEX-85505-5002"))
    )
    (comp (ref "R33")
      (value "56Ω")
      (footprint "eagle-import:0207_7")
      (fields (field (name "MANUFACTURER") "Joe Knows Electronics"))
      (libsource (lib "eagle-import") (part "RES-JKE"))
    )
    (comp (ref "R34")
      (value "3.9Ω")
      (footprint "eagle-import:0207_7")
      (fields (field (name "MANUFACTURER") "Joe Knows Electronics"))
      (libsource (lib "eagle-import") (part "RES-JKE"))
    )
    (comp (ref "R35")
      (value "56Ω")
      (footprint "eagle-import:0207_7")
      (fields (field (name "MANUFACTURER") "Joe Knows Electronics"))
      (libsource (lib "eagle-import") (part "RES-JKE"))
    )
    (comp (ref "R36")
      (value "3.9Ω")
      (footprint "eagle-import:0207_7")
      (fields (field (name "MANUFACTURER") "Joe Knows Electronics"))
      (libsource (lib "eagle-import") (part "RES-JKE"))
    )
    (comp (ref "SW1")
      (value "CTS-204-211ST")
      (footprint "eagle-import:204-211ST")
      (fields (field (name "MANUFACTURER") "CTS"))
      (libsource (lib "eagle-import") (part "CTS-204-211ST"))
    )
    (comp (ref "TP44")
      (value "CANH")
      (footprint "eagle-import:TP-P1-20")
      (libsource (lib "eagle-import") (part "TEST-POINT"))
    )
    (comp (ref "TP45")
      (value "CANL")
      (footprint "eagle-import:TP-P1-20")
      (libsource (lib "eagle-import") (part "TEST-POINT"))
    )
    (comp (ref "TP46")
      (value "CAN_TX")
      (footprint "eagle-import:TP-P1-20")
      (libsource (lib "eagle-import") (part "TEST-POINT"))
    )
    (comp (ref "TP47")
      (value "CAN_RX")
      (footprint "eagle-import:TP-P1-20")
      (libsource (lib "eagle-import") (part "TEST-POINT"))
    )
    (comp (ref "U10")
      (value "MCP2551-I/SN")
      (footprint "eagle-import:SOIC127P600X175-8N")
      (fields (field (name "MANUFACTURER") "Microchip"))
      (libsource (lib "eagle-import") (part "MCP2551-I/SN"))
    )
    (comp (ref "C13")
      (value "6.8nF")
      (footprint "eagle-import:C050-025X075")
      (fields (field (name "MANUFACTURER") "joe Knows Electronics"))
      (libsource (lib "eagle-import") (part "CAP-JKE"))
    )
    (comp (ref "Q1")
      (value "PN2222A")
      (footprint "eagle-import:TO92-EBC")
      (fields (field (name "MANUFACTURER") "Fairchild"))
      (libsource (lib "eagle-import") (part "PN2222A"))
    )
    (comp (ref "Q2")
      (value "FJPF13009")
      (footprint "eagle-import:TO220")
      (fields (field (name "MANUFACTURER") "Fairchild"))
      (libsource (lib "eagle-import") (part "FJPF13009"))
    )
    (comp (ref "Q7")
      (value "ISL9V5036P3_F085")
      (footprint "eagle-import:TO220AB")
      (fields (field (name "MANUFACTURER") "Fairchild"))
      (libsource (lib "eagle-import") (part "ISL9V5036P3_F085"))
    )
    (comp (ref "R1")
      (value "82Ω")
      (footprint "eagle-import:0207_7")
      (fields (field (name "MANUFACTURER") "Joe Knows Electronics"))
      (libsource (lib "eagle-import") (part "RES-JKE"))
    )
    (comp (ref "R31")
      (value "10mΩ")
      (footprint "eagle-import:0514_15")
      (fields (field (name "MANUFACTURER") "Vishay Dale"))
      (libsource (lib "eagle-import") (part "VISHAY_DALE-LVR03R0100FE70"))
    )
    (comp (ref "R32")
      (value "10mΩ")
      (footprint "eagle-import:0514_15")
      (fields (field (name "MANUFACTURER") "Vishay Dale"))
      (libsource (lib "eagle-import") (part "VISHAY_DALE-LVR03R0100FE70"))
    )
    (comp (ref "R64")
      (value "220Ω")
      (footprint "eagle-import:0207_7")
      (fields (field (name "MANUFACTURER") "Joe Knows Electronics"))
      (libsource (lib "eagle-import") (part "RES-JKE"))
    )
    (comp (ref "R65")
      (value "390Ω")
      (footprint "eagle-import:0207_7")
      (fields (field (name "MANUFACTURER") "Joe Knows Electronics"))
      (libsource (lib "eagle-import") (part "RES-JKE"))
    )
    (comp (ref "TP14")
      (value "HALL")
      (footprint "eagle-import:TP-P1-20")
      (libsource (lib "eagle-import") (part "TEST-POINT"))
    )
    (comp (ref "TP16")
      (value "FUEL")
      (footprint "eagle-import:TP-P1-20")
      (libsource (lib "eagle-import") (part "TEST-POINT"))
    )
    (comp (ref "TP17")
      (value "FUEL_E")
      (footprint "eagle-import:TP-P1-20")
      (libsource (lib "eagle-import") (part "TEST-POINT"))
    )
    (comp (ref "TP18")
      (value "SPARK")
      (footprint "eagle-import:TP-P1-20")
      (libsource (lib "eagle-import") (part "TEST-POINT"))
    )
    (comp (ref "TP19")
      (value "SPARK_E")
      (footprint "eagle-import:TP-P1-20")
      (libsource (lib "eagle-import") (part "TEST-POINT"))
    )
    (comp (ref "D1")
      (value "GREEN")
      (footprint "eagle-import:LED,THRU-HOLE,R_A")
      (fields (field (name "MANUFACTURER") "Lite-On"))
      (libsource (lib "eagle-import") (part "LTL-533-11"))
    )
    (comp (ref "D2")
      (value "YELLOW")
      (footprint "eagle-import:LED,THRU-HOLE,R_A")
      (fields (field (name "MANUFACTURER") "Lite-On"))
      (libsource (lib "eagle-import") (part "LTL-553-11"))
    )
    (comp (ref "D3")
      (value "YELLOW")
      (footprint "eagle-import:LED,THRU-HOLE,R_A")
      (fields (field (name "MANUFACTURER") "Lite-On"))
      (libsource (lib "eagle-import") (part "LTL-553-11"))
    )
    (comp (ref "D4")
      (value "RED")
      (footprint "eagle-import:LED,THRU-HOLE,R_A")
      (fields (field (name "MANUFACTURER") "Lite-On"))
      (libsource (lib "eagle-import") (part "LTL-523-11"))
    )
    (comp (ref "D5")
      (value "RED")
      (footprint "eagle-import:LED,THRU-HOLE,R_A")
      (fields (field (name "MANUFACTURER") "Lite-On"))
      (libsource (lib "eagle-import") (part "LTL-523-11"))
    )
    (comp (ref "Q3")
      (value "PN2222A")
      (footprint "eagle-import:TO92-EBC")
      (fields (field (name "MANUFACTURER") "Fairchild"))
      (libsource (lib "eagle-import") (part "PN2222A"))
    )
    (comp (ref "Q4")
      (value "PN2222A")
      (footprint "eagle-import:TO92-EBC")
      (fields (field (name "MANUFACTURER") "Fairchild"))
      (libsource (lib "eagle-import") (part "PN2222A"))
    )
    (comp (ref "Q5")
      (value "PN2222A")
      (footprint "eagle-import:TO92-EBC")
      (fields (field (name "MANUFACTURER") "Fairchild"))
      (libsource (lib "eagle-import") (part "PN2222A"))
    )
    (comp (ref "Q6")
      (value "PN2222A")
      (footprint "eagle-import:TO92-EBC")
      (fields (field (name "MANUFACTURER") "Fairchild"))
      (libsource (lib "eagle-import") (part "PN2222A"))
    )
    (comp (ref "R22")
      (value "1.2kΩ")
      (footprint "eagle-import:0207_7")
      (fields (field (name "MANUFACTURER") "Joe Knows Electronics"))
      (libsource (lib "eagle-import") (part "RES-JKE"))
    )
    (comp (ref "R23")
      (value "150Ω")
      (footprint "eagle-import:0207_7")
      (fields (field (name "MANUFACTURER") "Joe Knows Electronics"))
      (libsource (lib "eagle-import") (part "RES-JKE"))
    )
    (comp (ref "R24")
      (value "150Ω")
      (footprint "eagle-import:0207_7")
      (fields (field (name "MANUFACTURER") "Joe Knows Electronics"))
      (libsource (lib "eagle-import") (part "RES-JKE"))
    )
    (comp (ref "R25")
      (value "1.2kΩ")
      (footprint "eagle-import:0207_7")
      (fields (field (name "MANUFACTURER") "Joe Knows Electronics"))
      (libsource (lib "eagle-import") (part "RES-JKE"))
    )
    (comp (ref "R26")
      (value "150Ω")
      (footprint "eagle-import:0207_7")
      (fields (field (name "MANUFACTURER") "Joe Knows Electronics"))
      (libsource (lib "eagle-import") (part "RES-JKE"))
    )
    (comp (ref "R27")
      (value "1.2kΩ")
      (footprint "eagle-import:0207_7")
      (fields (field (name "MANUFACTURER") "Joe Knows Electronics"))
      (libsource (lib "eagle-import") (part "RES-JKE"))
    )
    (comp (ref "R28")
      (value "150Ω")
      (footprint "eagle-import:0207_7")
      (fields (field (name "MANUFACTURER") "Joe Knows Electronics"))
      (libsource (lib "eagle-import") (part "RES-JKE"))
    )
    (comp (ref "R29")
      (value "1.2kΩ")
      (footprint "eagle-import:0207_7")
      (fields (field (name "MANUFACTURER") "Joe Knows Electronics"))
      (libsource (lib "eagle-import") (part "RES-JKE"))
    )
    (comp (ref "R30")
      (value "150Ω")
      (footprint "eagle-import:0207_7")
      (fields (field (name "MANUFACTURER") "Joe Knows Electronics"))
      (libsource (lib "eagle-import") (part "RES-JKE"))
    )
    (comp (ref "TP48")
      (value "SPARK_LED")
      (footprint "eagle-import:TP-P1-20")
      (libsource (lib "eagle-import") (part "TEST-POINT"))
    )
    (comp (ref "TP49")
      (value "FUEL_LED")
      (footprint "eagle-import:TP-P1-20")
      (libsource (lib "eagle-import") (part "TEST-POINT"))
    )
    (comp (ref "TP50")
      (value "REV_LIMIT_LED")
      (footprint "eagle-import:TP-P1-20")
      (libsource (lib "eagle-import") (part "TEST-POINT"))
    )
    (comp (ref "TP51")
      (value "KILL_SW_LED")
      (footprint "eagle-import:TP-P1-20")
      (libsource (lib "eagle-import") (part "TEST-POINT"))
    )
    (comp (ref "C9")
      (value "330pF")
      (footprint "eagle-import:C050-025X075")
      (fields (field (name "MANUFACTURER") "joe Knows Electronics"))
      (libsource (lib "eagle-import") (part "CAP-JKE"))
    )
    (comp (ref "C14")
      (value "10nF")
      (footprint "eagle-import:C050-025X075")
      (fields (field (name "MANUFACTURER") "joe Knows Electronics"))
      (libsource (lib "eagle-import") (part "CAP-JKE"))
    )
    (comp (ref "C15")
      (value "330pF")
      (footprint "eagle-import:C050-025X075")
      (fields (field (name "MANUFACTURER") "joe Knows Electronics"))
      (libsource (lib "eagle-import") (part "CAP-JKE"))
    )
    (comp (ref "C16")
      (value "10nF")
      (footprint "eagle-import:C050-025X075")
      (fields (field (name "MANUFACTURER") "joe Knows Electronics"))
      (libsource (lib "eagle-import") (part "CAP-JKE"))
    )
    (comp (ref "C17")
      (value "330pF")
      (footprint "eagle-import:C050-025X075")
      (fields (field (name "MANUFACTURER") "joe Knows Electronics"))
      (libsource (lib "eagle-import") (part "CAP-JKE"))
    )
    (comp (ref "C18")
      (value "10nF")
      (footprint "eagle-import:C050-025X075")
      (fields (field (name "MANUFACTURER") "joe Knows Electronics"))
      (libsource (lib "eagle-import") (part "CAP-JKE"))
    )
    (comp (ref "C19")
      (value "330pF")
      (footprint "eagle-import:C050-025X075")
      (fields (field (name "MANUFACTURER") "joe Knows Electronics"))
      (libsource (lib "eagle-import") (part "CAP-JKE"))
    )
    (comp (ref "R20")
      (value "180kΩ")
      (footprint "eagle-import:0207_7")
      (fields (field (name "MANUFACTURER") "Joe Knows Electronics"))
      (libsource (lib "eagle-import") (part "RES-JKE"))
    )
    (comp (ref "R21")
      (value "120kΩ")
      (footprint "eagle-import:0207_7")
      (fields (field (name "MANUFACTURER") "Joe Knows Electronics"))
      (libsource (lib "eagle-import") (part "RES-JKE"))
    )
    (comp (ref "R39")
      (value "470Ω")
      (footprint "eagle-import:0207_7")
      (fields (field (name "MANUFACTURER") "Joe Knows Electronics"))
      (libsource (lib "eagle-import") (part "RES-JKE"))
    )
    (comp (ref "R66")
      (value "68kΩ")
      (footprint "eagle-import:0207_7")
      (fields (field (name "MANUFACTURER") "Joe Knows Electronics"))
      (libsource (lib "eagle-import") (part "RES-JKE"))
    )
    (comp (ref "R67")
      (value "3.9kΩ")
      (footprint "eagle-import:0207_7")
      (fields (field (name "MANUFACTURER") "Joe Knows Electronics"))
      (libsource (lib "eagle-import") (part "RES-JKE"))
    )
    (comp (ref "R68")
      (value "39kΩ")
      (footprint "eagle-import:0207_7")
      (fields (field (name "MANUFACTURER") "Joe Knows Electronics"))
      (libsource (lib "eagle-import") (part "RES-JKE"))
    )
    (comp (ref "R69")
      (value "82kΩ")
      (footprint "eagle-import:0207_7")
      (fields (field (name "MANUFACTURER") "Joe Knows Electronics"))
      (libsource (lib "eagle-import") (part "RES-JKE"))
    )
    (comp (ref "R70")
      (value "82kΩ")
      (footprint "eagle-import:0207_7")
      (fields (field (name "MANUFACTURER") "Joe Knows Electronics"))
      (libsource (lib "eagle-import") (part "RES-JKE"))
    )
    (comp (ref "R71")
      (value "120kΩ")
      (footprint "eagle-import:0207_7")
      (fields (field (name "MANUFACTURER") "Joe Knows Electronics"))
      (libsource (lib "eagle-import") (part "RES-JKE"))
    )
    (comp (ref "R72")
      (value "56kΩ")
      (footprint "eagle-import:0207_7")
      (fields (field (name "MANUFACTURER") "Joe Knows Electronics"))
      (libsource (lib "eagle-import") (part "RES-JKE"))
    )
    (comp (ref "R73")
      (value "180kΩ")
      (footprint "eagle-import:0207_7")
      (fields (field (name "MANUFACTURER") "Joe Knows Electronics"))
      (libsource (lib "eagle-import") (part "RES-JKE"))
    )
    (comp (ref "R74")
      (value "120kΩ")
      (footprint "eagle-import:0207_7")
      (fields (field (name "MANUFACTURER") "Joe Knows Electronics"))
      (libsource (lib "eagle-import") (part "RES-JKE"))
    )
    (comp (ref "R75")
      (value "68kΩ")
      (footprint "eagle-import:0207_7")
      (fields (field (name "MANUFACTURER") "Joe Knows Electronics"))
      (libsource (lib "eagle-import") (part "RES-JKE"))
    )
    (comp (ref "R76")
      (value "3.9kΩ")
      (footprint "eagle-import:0207_7")
      (fields (field (name "MANUFACTURER") "Joe Knows Electronics"))
      (libsource (lib "eagle-import") (part "RES-JKE"))
    )
    (comp (ref "R77")
      (value "39kΩ")
      (footprint "eagle-import:0207_7")
      (fields (field (name "MANUFACTURER") "Joe Knows Electronics"))
      (libsource (lib "eagle-import") (part "RES-JKE"))
    )
    (comp (ref "R78")
      (value "82kΩ")
      (footprint "eagle-import:0207_7")
      (fields (field (name "MANUFACTURER") "Joe Knows Electronics"))
      (libsource (lib "eagle-import") (part "RES-JKE"))
    )
    (comp (ref "R79")
      (value "82kΩ")
      (footprint "eagle-import:0207_7")
      (fields (field (name "MANUFACTURER") "Joe Knows Electronics"))
      (libsource (lib "eagle-import") (part "RES-JKE"))
    )
    (comp (ref "R80")
      (value "120kΩ")
      (footprint "eagle-import:0207_7")
      (fields (field (name "MANUFACTURER") "Joe Knows Electronics"))
      (libsource (lib "eagle-import") (part "RES-JKE"))
    )
    (comp (ref "R81")
      (value "56kΩ")
      (footprint "eagle-import:0207_7")
      (fields (field (name "MANUFACTURER") "Joe Knows Electronics"))
      (libsource (lib "eagle-import") (part "RES-JKE"))
    )
    (comp (ref "R82")
      (value "180kΩ")
      (footprint "eagle-import:0207_7")
      (fields (field (name "MANUFACTURER") "Joe Knows Electronics"))
      (libsource (lib "eagle-import") (part "RES-JKE"))
    )
    (comp (ref "R83")
      (value "120kΩ")
      (footprint "eagle-import:0207_7")
      (fields (field (name "MANUFACTURER") "Joe Knows Electronics"))
      (libsource (lib "eagle-import") (part "RES-JKE"))
    )
    (comp (ref "R84")
      (value "68kΩ")
      (footprint "eagle-import:0207_7")
      (fields (field (name "MANUFACTURER") "Joe Knows Electronics"))
      (libsource (lib "eagle-import") (part "RES-JKE"))
    )
    (comp (ref "R85")
      (value "3.9kΩ")
      (footprint "eagle-import:0207_7")
      (fields (field (name "MANUFACTURER") "Joe Knows Electronics"))
      (libsource (lib "eagle-import") (part "RES-JKE"))
    )
    (comp (ref "R86")
      (value "39kΩ")
      (footprint "eagle-import:0207_7")
      (fields (field (name "MANUFACTURER") "Joe Knows Electronics"))
      (libsource (lib "eagle-import") (part "RES-JKE"))
    )
    (comp (ref "R87")
      (value "82kΩ")
      (footprint "eagle-import:0207_7")
      (fields (field (name "MANUFACTURER") "Joe Knows Electronics"))
      (libsource (lib "eagle-import") (part "RES-JKE"))
    )
    (comp (ref "R88")
      (value "82kΩ")
      (footprint "eagle-import:0207_7")
      (fields (field (name "MANUFACTURER") "Joe Knows Electronics"))
      (libsource (lib "eagle-import") (part "RES-JKE"))
    )
    (comp (ref "R89")
      (value "120kΩ")
      (footprint "eagle-import:0207_7")
      (fields (field (name "MANUFACTURER") "Joe Knows Electronics"))
      (libsource (lib "eagle-import") (part "RES-JKE"))
    )
    (comp (ref "R90")
      (value "56kΩ")
      (footprint "eagle-import:0207_7")
      (fields (field (name "MANUFACTURER") "Joe Knows Electronics"))
      (libsource (lib "eagle-import") (part "RES-JKE"))
    )
    (comp (ref "TP23")
      (value "MAP")
      (footprint "eagle-import:TP-P1-20")
      (libsource (lib "eagle-import") (part "TEST-POINT"))
    )
    (comp (ref "TP24")
      (value "MAP_FIL")
      (footprint "eagle-import:TP-P1-20")
      (libsource (lib "eagle-import") (part "TEST-POINT"))
    )
    (comp (ref "TP25")
      (value "O2")
      (footprint "eagle-import:TP-P1-20")
      (libsource (lib "eagle-import") (part "TEST-POINT"))
    )
    (comp (ref "TP26")
      (value "O2_FIL")
      (footprint "eagle-import:TP-P1-20")
      (libsource (lib "eagle-import") (part "TEST-POINT"))
    )
    (comp (ref "TP27")
      (value "TPS")
      (footprint "eagle-import:TP-P1-20")
      (libsource (lib "eagle-import") (part "TEST-POINT"))
    )
    (comp (ref "TP28")
      (value "TPS_FIL")
      (footprint "eagle-import:TP-P1-20")
      (libsource (lib "eagle-import") (part "TEST-POINT"))
    )
    (comp (ref "U7")
      (value "LM358")
      (footprint "eagle-import:SOP08")
      (fields (field (name "MANUFACTURER") "Texas Instruments"))
      (libsource (lib "eagle-import") (part "LM358"))
    )
    (comp (ref "U8")
      (value "LM358")
      (footprint "eagle-import:SOP08")
      (fields (field (name "MANUFACTURER") "Texas Instruments"))
      (libsource (lib "eagle-import") (part "LM358"))
    )
    (comp (ref "U9")
      (value "LM358")
      (footprint "eagle-import:SOP08")
      (fields (field (name "MANUFACTURER") "Texas Instruments"))
      (libsource (lib "eagle-import") (part "LM358"))
    )
  )
  (nets
    (net (code "1") (name "+3V3") (class "Default")
      (node (ref "C2") (pin "1") (pinfunction "1_1") (pintype "passive"))
      (node (ref "J4") (pin "2") (pinfunction "2_2") (pintype "passive"))
      (node (ref "J4") (pin "4") (pinfunction "4_4") (pintype "passive"))
      (node (ref "TP3") (pin "TP") (pinfunction "TP_TP") (pintype "input"))
      (node (ref "U1") (pin "1") (pinfunction "VCCA_1") (pintype "power_in"))
      (node (ref "U1") (pin "8") (pinfunction "OE_8") (pintype "input"))
    )
    (net (code "2") (name "+5V") (class "Default")
      (node (ref "C1") (pin "1") (pinfunction "1_1") (pintype "passive"))
      (node (ref "C14") (pin "1") (pinfunction "1_1") (pintype "passive"))
      (node (ref "C16") (pin "1") (pinfunction "1_1") (pintype "passive"))
      (node (ref "C18") (pin "1") (pinfunction "1_1") (pintype "passive"))
      (node (ref "C3") (pin "1") (pinfunction "1_1") (pintype "passive"))
      (node (ref "C33") (pin "1") (pinfunction "1_1") (pintype "passive"))
      (node (ref "C5") (pin "1") (pinfunction "1_1") (pintype "passive"))
      (node (ref "J4") (pin "5") (pinfunction "5_5") (pintype "passive"))
      (node (ref "J8") (pin "2") (pinfunction "2_2") (pintype "passive"))
      (node (ref "Q1") (pin "C") (pinfunction "C_C") (pintype "passive"))
      (node (ref "R13") (pin "1") (pinfunction "1_1") (pintype "passive"))
      (node (ref "R18") (pin "1") (pinfunction "1_1") (pintype "passive"))
      (node (ref "R23") (pin "1") (pinfunction "1_1") (pintype "passive"))
      (node (ref "R24") (pin "1") (pinfunction "1_1") (pintype "passive"))
      (node (ref "R26") (pin "1") (pinfunction "1_1") (pintype "passive"))
      (node (ref "R28") (pin "1") (pinfunction "1_1") (pintype "passive"))
      (node (ref "R30") (pin "1") (pinfunction "1_1") (pintype "passive"))
      (node (ref "R37") (pin "2") (pinfunction "2_2") (pintype "passive"))
      (node (ref "R38") (pin "2") (pinfunction "2_2") (pintype "passive"))
      (node (ref "R4") (pin "1") (pinfunction "1_1") (pintype "passive"))
      (node (ref "R64") (pin "2") (pinfunction "2_2") (pintype "passive"))
      (node (ref "R66") (pin "1") (pinfunction "1_1") (pintype "passive"))
      (node (ref "R71") (pin "1") (pinfunction "1_1") (pintype "passive"))
      (node (ref "R75") (pin "1") (pinfunction "1_1") (pintype "passive"))
      (node (ref "R80") (pin "1") (pinfunction "1_1") (pintype "passive"))
      (node (ref "R84") (pin "1") (pinfunction "1_1") (pintype "passive"))
      (node (ref "R89") (pin "1") (pinfunction "1_1") (pintype "passive"))
      (node (ref "R9") (pin "1") (pinfunction "1_1") (pintype "passive"))
      (node (ref "TP2") (pin "TP") (pinfunction "TP_TP") (pintype "input"))
      (node (ref "U1") (pin "14") (pinfunction "VCCB_14") (pintype "power_in"))
      (node (ref "U10") (pin "3") (pinfunction "VDD_3") (pintype "power_in"))
      (node (ref "U2") (pin "8") (pinfunction "VDD_8") (pintype "power_in"))
      (node (ref "U5") (pin "8") (pinfunction "VDD_8") (pintype "power_in"))
      (node (ref "U7") (pin "8") (pinfunction "VDD_8") (pintype "power_in"))
      (node (ref "U8") (pin "8") (pinfunction "VDD_8") (pintype "power_in"))
      (node (ref "U9") (pin "8") (pinfunction "VDD_8") (pintype "power_in"))
    )
    (net (code "3") (name "+12V") (class "Default")
      (node (ref "C35") (pin "1") (pinfunction "1_1") (pintype "passive"))
      (node (ref "C36") (pin "1") (pinfunction "1_1") (pintype "passive"))
      (node (ref "J10") (pin "2") (pinfunction "2_2") (pintype "passive"))
      (node (ref "J10") (pin "4") (pinfunction "4_4") (pintype "passive"))
      (node (ref "J4") (pin "8") (pinfunction "8_8") (pintype "passive"))
      (node (ref "J9") (pin "2") (pinfunction "2_2") (pintype "passive"))
      (node (ref "J9") (pin "4") (pinfunction "4_4") (pintype "passive"))
      (node (ref "TP1") (pin "TP") (pinfunction "TP_TP") (pintype "input"))
    )
    (net (code "4") (name "CANH") (class "Default")
      (node (ref "J10") (pin "8") (pinfunction "8_8") (pintype "passive"))
      (node (ref "J9") (pin "8") (pinfunction "8_8") (pintype "passive"))
      (node (ref "SW1") (pin "1") (pinfunction "1_1") (pintype "passive"))
      (node (ref "TP44") (pin "TP") (pinfunction "TP_TP") (pintype "input"))
      (node (ref "U10") (pin "7") (pinfunction "CANH_7") (pintype "bidirectional"))
    )
    (net (code "5") (name "CANL") (class "Default")
      (node (ref "J10") (pin "7") (pinfunction "7_7") (pintype "passive"))
      (node (ref "J9") (pin "7") (pinfunction "7_7") (pintype "passive"))
      (node (ref "SW1") (pin "3") (pinfunction "3_3") (pintype "passive"))
      (node (ref "TP45") (pin "TP") (pinfunction "TP_TP") (pintype "input"))
      (node (ref "U10") (pin "6") (pinfunction "CANL_6") (pintype "bidirectional"))
    )
    (net (code "6") (name "CAN_RX") (class "Default")
      (node (ref "J6") (pin "7") (pinfunction "7_7") (pintype "passive"))
      (node (ref "TP47") (pin "TP") (pinfunction "TP_TP") (pintype "input"))
      (node (ref "U10") (pin "4") (pinfunction "RXD_4") (pintype "output"))
    )
    (net (code "7") (name "CAN_TX") (class "Default")
      (node (ref "J6") (pin "8") (pinfunction "8_8") (pintype "passive"))
      (node (ref "TP46") (pin "TP") (pinfunction "TP_TP") (pintype "input"))
      (node (ref "U10") (pin "1") (pinfunction "TXD_1") (pintype "input"))
    )
    (net (code "8") (name "CS1_3V3") (class "Default")
      (node (ref "J2") (pin "4") (pinfunction "4_4") (pintype "passive"))
      (node (ref "TP13") (pin "TP") (pinfunction "TP_TP") (pintype "input"))
      (node (ref "U1") (pin "5") (pinfunction "A4_5") (pintype "input"))
    )
    (net (code "9") (name "CS1_5V") (class "Default")
      (node (ref "TP39") (pin "TP") (pinfunction "TP_TP") (pintype "input"))
      (node (ref "U1") (pin "10") (pinfunction "B4_10") (pintype "output"))
    )
    (net (code "10") (name "ECT") (class "Default")
      (node (ref "C7") (pin "1") (pinfunction "1_1") (pintype "passive"))
      (node (ref "R2") (pin "1") (pinfunction "1_1") (pintype "passive"))
      (node (ref "R37") (pin "1") (pinfunction "1_1") (pintype "passive"))
      (node (ref "TP15") (pin "TP") (pinfunction "TP_TP") (pintype "input"))
    )
    (net (code "11") (name "ECT_FIL") (class "Default")
      (node (ref "C4") (pin "2") (pinfunction "2_2") (pintype "passive"))
      (node (ref "R8") (pin "1") (pinfunction "1_1") (pintype "passive"))
      (node (ref "TP20") (pin "TP") (pinfunction "TP_TP") (pintype "input"))
      (node (ref "U5") (pin "7") (pinfunction "VOUTB_7") (pintype "passive"))
    )
    (net (code "12") (name "FUEL") (class "Default")
      (node (ref "J1") (pin "10") (pinfunction "10_10") (pintype "passive"))
      (node (ref "R1") (pin "1") (pinfunction "1_1") (pintype "passive"))
      (node (ref "TP16") (pin "TP") (pinfunction "TP_TP") (pintype "input"))
    )
    (net (code "13") (name "FUEL_INJ") (class "Default")
      (node (ref "Q2") (pin "2") (pinfunction "C_2") (pintype "passive"))
    )
    (net (code "14") (name "FUEL_LED") (class "Default")
      (node (ref "R25") (pin "1") (pinfunction "1_1") (pintype "passive"))
      (node (ref "TP49") (pin "TP") (pinfunction "TP_TP") (pintype "input"))
    )
    (net (code "15") (name "GND") (class "Default")
      (node (ref "C1") (pin "2") (pinfunction "2_2") (pintype "passive"))
      (node (ref "C10") (pin "2") (pinfunction "2_2") (pintype "passive"))
      (node (ref "C13") (pin "2") (pinfunction "2_2") (pintype "passive"))
      (node (ref "C14") (pin "2") (pinfunction "2_2") (pintype "passive"))
      (node (ref "C16") (pin "2") (pinfunction "2_2") (pintype "passive"))
      (node (ref "C18") (pin "2") (pinfunction "2_2") (pintype "passive"))
      (node (ref "C2") (pin "2") (pinfunction "2_2") (pintype "passive"))
      (node (ref "C3") (pin "2") (pinfunction "2_2") (pintype "passive"))
      (node (ref "C33") (pin "2") (pinfunction "2_2") (pintype "passive"))
      (node (ref "C34") (pin "2") (pinfunction "2_2") (pintype "passive"))
      (node (ref "C35") (pin "2") (pinfunction "2_2") (pintype "passive"))
      (node (ref "C36") (pin "2") (pinfunction "2_2") (pintype "passive"))
      (node (ref "C5") (pin "2") (pinfunction "2_2") (pintype "passive"))
      (node (ref "C7") (pin "2") (pinfunction "2_2") (pintype "passive"))
      (node (ref "C8") (pin "2") (pinfunction "2_2") (pintype "passive"))
      (node (ref "C9") (pin "2") (pinfunction "2_2") (pintype "passive"))
      (node (ref "D1") (pin "CATHODE") (pinfunction "CATHODE_CATHODE") (pintype "passive"))
      (node (ref "J1") (pin "4") (pinfunction "4_4") (pintype "passive"))
      (node (ref "J10") (pin "1") (pinfunction "1_1") (pintype "power_in"))
      (node (ref "J10") (pin "10") (pinfunction "9_10") (pintype "passive"))
      (node (ref "J10") (pin "5") (pinfunction "5_5") (pintype "passive"))
      (node (ref "J10") (pin "9") (pinfunction "9_9") (pintype "passive"))
      (node (ref "J4") (pin "6") (pinfunction "6_6") (pintype "passive"))
      (node (ref "J4") (pin "7") (pinfunction "7_7") (pintype "passive"))
      (node (ref "J8") (pin "6") (pinfunction "6_6") (pintype "passive"))
      (node (ref "J9") (pin "1") (pinfunction "1_1") (pintype "power_in"))
      (node (ref "J9") (pin "10") (pinfunction "9_10") (pintype "passive"))
      (node (ref "J9") (pin "5") (pinfunction "5_5") (pintype "passive"))
      (node (ref "J9") (pin "9") (pinfunction "9_9") (pintype "passive"))
      (node (ref "Q3") (pin "E") (pinfunction "E_E") (pintype "passive"))
      (node (ref "Q4") (pin "E") (pinfunction "E_E") (pintype "passive"))
      (node (ref "Q5") (pin "E") (pinfunction "E_E") (pintype "passive"))
      (node (ref "Q6") (pin "E") (pinfunction "E_E") (pintype "passive"))
      (node (ref "R10") (pin "1") (pinfunction "1_1") (pintype "passive"))
      (node (ref "R15") (pin "1") (pinfunction "1_1") (pintype "passive"))
      (node (ref "R19") (pin "1") (pinfunction "1_1") (pintype "passive"))
      (node (ref "R31") (pin "1") (pinfunction "1_1") (pintype "passive"))
      (node (ref "R32") (pin "1") (pinfunction "1_1") (pintype "passive"))
      (node (ref "R39") (pin "1") (pinfunction "1_1") (pintype "passive"))
      (node (ref "R41") (pin "1") (pinfunction "1_1") (pintype "passive"))
      (node (ref "R6") (pin "1") (pinfunction "1_1") (pintype "passive"))
      (node (ref "R65") (pin "1") (pinfunction "1_1") (pintype "passive"))
      (node (ref "R68") (pin "1") (pinfunction "1_1") (pintype "passive"))
      (node (ref "R72") (pin "1") (pinfunction "1_1") (pintype "passive"))
      (node (ref "R77") (pin "1") (pinfunction "1_1") (pintype "passive"))
      (node (ref "R81") (pin "1") (pinfunction "1_1") (pintype "passive"))
      (node (ref "R86") (pin "1") (pinfunction "1_1") (pintype "passive"))
      (node (ref "R90") (pin "1") (pinfunction "1_1") (pintype "passive"))
      (node (ref "TP4") (pin "TP") (pinfunction "TP_TP") (pintype "input"))
      (node (ref "TP5") (pin "TP") (pinfunction "TP_TP") (pintype "input"))
      (node (ref "TP6") (pin "TP") (pinfunction "TP_TP") (pintype "input"))
      (node (ref "U1") (pin "7") (pinfunction "GND_7") (pintype "passive"))
      (node (ref "U10") (pin "2") (pinfunction "VSS_2") (pintype "passive"))
      (node (ref "U10") (pin "8") (pinfunction "RS_8") (pintype "input"))
      (node (ref "U2") (pin "4") (pinfunction "VSS_4") (pintype "power_in"))
      (node (ref "U5") (pin "4") (pinfunction "VSS_4") (pintype "power_in"))
      (node (ref "U7") (pin "4") (pinfunction "VSS_4") (pintype "power_in"))
      (node (ref "U8") (pin "4") (pinfunction "VSS_4") (pintype "power_in"))
      (node (ref "U9") (pin "4") (pinfunction "VSS_4") (pintype "power_in"))
    )
    (net (code "16") (name "HALL") (class "Default")
      (node (ref "C13") (pin "1") (pinfunction "1_1") (pintype "passive"))
      (node (ref "J2") (pin "3") (pinfunction "3_3") (pintype "passive"))
      (node (ref "R64") (pin "1") (pinfunction "1_1") (pintype "passive"))
      (node (ref "R65") (pin "2") (pinfunction "2_2") (pintype "passive"))
      (node (ref "TP14") (pin "TP") (pinfunction "TP_TP") (pintype "input"))
    )
    (net (code "17") (name "IAT") (class "Default")
      (node (ref "C8") (pin "1") (pinfunction "1_1") (pintype "passive"))
      (node (ref "R11") (pin "1") (pinfunction "1_1") (pintype "passive"))
      (node (ref "R38") (pin "1") (pinfunction "1_1") (pintype "passive"))
      (node (ref "TP21") (pin "TP") (pinfunction "TP_TP") (pintype "input"))
    )
    (net (code "18") (name "IAT_FIL") (class "Default")
      (node (ref "C6") (pin "2") (pinfunction "2_2") (pintype "passive"))
      (node (ref "R17") (pin "1") (pinfunction "1_1") (pintype "passive"))
      (node (ref "TP22") (pin "TP") (pinfunction "TP_TP") (pintype "input"))
      (node (ref "U2") (pin "7") (pinfunction "VOUTB_7") (pintype "passive"))
    )
    (net (code "19") (name "IGN_COIL") (class "Default")
      (node (ref "Q7") (pin "2") (pinfunction "C_2") (pintype "passive"))
    )
    (net (code "20") (name "KILL_SW") (class "Default")
      (node (ref "R40") (pin "1") (pinfunction "1_1") (pintype "passive"))
      (node (ref "TP7") (pin "TP") (pinfunction "TP_TP") (pintype "input"))
    )
    (net (code "21") (name "KILL_SW_3V3") (class "Default")
      (node (ref "C10") (pin "1") (pinfunction "1_1") (pintype "passive"))
      (node (ref "R40") (pin "2") (pinfunction "2_2") (pintype "passive"))
      (node (ref "R41") (pin "2") (pinfunction "2_2") (pintype "passive"))
      (node (ref "TP8") (pin "TP") (pinfunction "TP_TP") (pintype "input"))
    )
    (net (code "22") (name "KILL_SW_LED") (class "Default")
      (node (ref "R29") (pin "1") (pinfunction "1_1") (pintype "passive"))
      (node (ref "TP51") (pin "TP") (pinfunction "TP_TP") (pintype "input"))
    )
    (net (code "23") (name "MAP") (class "Default")
      (node (ref "C9") (pin "1") (pinfunction "1_1") (pintype "passive"))
      (node (ref "R20") (pin "1") (pinfunction "1_1") (pintype "passive"))
      (node (ref "R39") (pin "2") (pinfunction "2_2") (pintype "passive"))
      (node (ref "TP23") (pin "TP") (pinfunction "TP_TP") (pintype "input"))
    )
    (net (code "24") (name "MAP_FIL") (class "Default")
      (node (ref "C15") (pin "2") (pinfunction "2_2") (pintype "passive"))
      (node (ref "R70") (pin "1") (pinfunction "1_1") (pintype "passive"))
      (node (ref "TP24") (pin "TP") (pinfunction "TP_TP") (pintype "input"))
      (node (ref "U7") (pin "7") (pinfunction "VOUTB_7") (pintype "passive"))
    )
    (net (code "25") (name "MISO_3V3") (class "Default")
      (node (ref "J8") (pin "1") (pinfunction "1_1") (pintype "passive"))
      (node (ref "TP11") (pin "TP") (pinfunction "TP_TP") (pintype "input"))
      (node (ref "U1") (pin "4") (pinfunction "A3_4") (pintype "input"))
    )
    (net (code "26") (name "MISO_5V") (class "Default")
      (node (ref "TP38") (pin "TP") (pinfunction "TP_TP") (pintype "input"))
      (node (ref "U1") (pin "11") (pinfunction "B3_11") (pintype "output"))
    )
    (net (code "27") (name "MOSI_3V3") (class "Default")
      (node (ref "J8") (pin "4") (pinfunction "4_4") (pintype "passive"))
      (node (ref "TP10") (pin "TP") (pinfunction "TP_TP") (pintype "input"))
      (node (ref "U1") (pin "2") (pinfunction "A1_2") (pintype "input"))
    )
    (net (code "28") (name "MOSI_5V") (class "Default")
      (node (ref "TP36") (pin "TP") (pinfunction "TP_TP") (pintype "input"))
      (node (ref "U1") (pin "13") (pinfunction "B1_13") (pintype "output"))
    )
    (net (code "29") (name "Net-(C34-Pad1)") (class "Default")
      (node (ref "C34") (pin "1") (pinfunction "1_1") (pintype "passive"))
      (node (ref "R34") (pin "2") (pinfunction "2_2") (pintype "passive"))
      (node (ref "R36") (pin "1") (pinfunction "1_1") (pintype "passive"))
    )
    (net (code "30") (name "Net-(D1-PadANODE)") (class "Default")
      (node (ref "D1") (pin "ANODE") (pinfunction "ANODE_ANODE") (pintype "passive"))
      (node (ref "R23") (pin "2") (pinfunction "2_2") (pintype "passive"))
    )
    (net (code "31") (name "Net-(D2-PadANODE)") (class "Default")
      (node (ref "D2") (pin "ANODE") (pinfunction "ANODE_ANODE") (pintype "passive"))
      (node (ref "R24") (pin "2") (pinfunction "2_2") (pintype "passive"))
    )
    (net (code "32") (name "Net-(D2-PadCATHODE)") (class "Default")
      (node (ref "D2") (pin "CATHODE") (pinfunction "CATHODE_CATHODE") (pintype "passive"))
      (node (ref "Q3") (pin "C") (pinfunction "C_C") (pintype "passive"))
    )
    (net (code "33") (name "Net-(D3-PadANODE)") (class "Default")
      (node (ref "D3") (pin "ANODE") (pinfunction "ANODE_ANODE") (pintype "passive"))
      (node (ref "R26") (pin "2") (pinfunction "2_2") (pintype "passive"))
    )
    (net (code "34") (name "Net-(D3-PadCATHODE)") (class "Default")
      (node (ref "D3") (pin "CATHODE") (pinfunction "CATHODE_CATHODE") (pintype "passive"))
      (node (ref "Q4") (pin "C") (pinfunction "C_C") (pintype "passive"))
    )
    (net (code "35") (name "Net-(D4-PadANODE)") (class "Default")
      (node (ref "D4") (pin "ANODE") (pinfunction "ANODE_ANODE") (pintype "passive"))
      (node (ref "R28") (pin "2") (pinfunction "2_2") (pintype "passive"))
    )
    (net (code "36") (name "Net-(D4-PadCATHODE)") (class "Default")
      (node (ref "D4") (pin "CATHODE") (pinfunction "CATHODE_CATHODE") (pintype "passive"))
      (node (ref "Q5") (pin "C") (pinfunction "C_C") (pintype "passive"))
    )
    (net (code "37") (name "Net-(D5-PadANODE)") (class "Default")
      (node (ref "D5") (pin "ANODE") (pinfunction "ANODE_ANODE") (pintype "passive"))
      (node (ref "R30") (pin "2") (pinfunction "2_2") (pintype "passive"))
    )
    (net (code "38") (name "Net-(D5-PadCATHODE)") (class "Default")
      (node (ref "D5") (pin "CATHODE") (pinfunction "CATHODE_CATHODE") (pintype "passive"))
      (node (ref "Q6") (pin "C") (pinfunction "C_C") (pintype "passive"))
    )
    (net (code "39") (name "Net-(Q1-PadB)") (class "Default")
      (node (ref "Q1") (pin "B") (pinfunction "B_B") (pintype "passive"))
      (node (ref "R1") (pin "2") (pinfunction "2_2") (pintype "passive"))
    )
    (net (code "40") (name "Net-(Q2-B)") (class "Default")
      (node (ref "Q1") (pin "E") (pinfunction "E_E") (pintype "passive"))
      (node (ref "Q2") (pin "1") (pinfunction "B_1") (pintype "passive"))
    )
    (net (code "41") (name "Net-(Q2-E)") (class "Default")
      (node (ref "Q2") (pin "3") (pinfunction "E_3") (pintype "passive"))
      (node (ref "R31") (pin "2") (pinfunction "2_2") (pintype "passive"))
      (node (ref "TP17") (pin "TP") (pinfunction "TP_TP") (pintype "input"))
    )
    (net (code "42") (name "Net-(Q3-PadB)") (class "Default")
      (node (ref "Q3") (pin "B") (pinfunction "B_B") (pintype "passive"))
      (node (ref "R22") (pin "2") (pinfunction "2_2") (pintype "passive"))
    )
    (net (code "43") (name "Net-(Q4-PadB)") (class "Default")
      (node (ref "Q4") (pin "B") (pinfunction "B_B") (pintype "passive"))
      (node (ref "R25") (pin "2") (pinfunction "2_2") (pintype "passive"))
    )
    (net (code "44") (name "Net-(Q5-PadB)") (class "Default")
      (node (ref "Q5") (pin "B") (pinfunction "B_B") (pintype "passive"))
      (node (ref "R27") (pin "2") (pinfunction "2_2") (pintype "passive"))
    )
    (net (code "45") (name "Net-(Q6-PadB)") (class "Default")
      (node (ref "Q6") (pin "B") (pinfunction "B_B") (pintype "passive"))
      (node (ref "R29") (pin "2") (pinfunction "2_2") (pintype "passive"))
    )
    (net (code "46") (name "Net-(Q7-E)") (class "Default")
      (node (ref "Q7") (pin "3") (pinfunction "E_3") (pintype "passive"))
      (node (ref "R32") (pin "2") (pinfunction "2_2") (pintype "passive"))
      (node (ref "TP19") (pin "TP") (pinfunction "TP_TP") (pintype "input"))
    )
    (net (code "47") (name "Net-(R5-Pad1)") (class "Default")
      (node (ref "R5") (pin "1") (pinfunction "1_1") (pintype "passive"))
      (node (ref "R6") (pin "2") (pinfunction "2_2") (pintype "passive"))
    )
    (net (code "48") (name "Net-(R14-Pad1)") (class "Default")
      (node (ref "R14") (pin "1") (pinfunction "1_1") (pintype "passive"))
      (node (ref "R15") (pin "2") (pinfunction "2_2") (pintype "passive"))
    )
    (net (code "49") (name "Net-(R33-Pad1)") (class "Default")
      (node (ref "R33") (pin "1") (pinfunction "1_1") (pintype "passive"))
      (node (ref "R34") (pin "1") (pinfunction "1_1") (pintype "passive"))
    )
    (net (code "50") (name "Net-(R33-Pad2)") (class "Default")
      (node (ref "R33") (pin "2") (pinfunction "2_2") (pintype "passive"))
      (node (ref "SW1") (pin "2") (pinfunction "2_2") (pintype "passive"))
    )
    (net (code "51") (name "Net-(R35-Pad1)") (class "Default")
      (node (ref "R35") (pin "1") (pinfunction "1_1") (pintype "passive"))
      (node (ref "SW1") (pin "4") (pinfunction "4_4") (pintype "passive"))
    )
    (net (code "52") (name "Net-(R35-Pad2)") (class "Default")
      (node (ref "R35") (pin "2") (pinfunction "2_2") (pintype "passive"))
      (node (ref "R36") (pin "2") (pinfunction "2_2") (pintype "passive"))
    )
    (net (code "53") (name "Net-(R67-Pad1)") (class "Default")
      (node (ref "R67") (pin "1") (pinfunction "1_1") (pintype "passive"))
      (node (ref "R68") (pin "2") (pinfunction "2_2") (pintype "passive"))
    )
    (net (code "54") (name "Net-(R76-Pad1)") (class "Default")
      (node (ref "R76") (pin "1") (pinfunction "1_1") (pintype "passive"))
      (node (ref "R77") (pin "2") (pinfunction "2_2") (pintype "passive"))
    )
    (net (code "55") (name "Net-(R85-Pad1)") (class "Default")
      (node (ref "R85") (pin "1") (pinfunction "1_1") (pintype "passive"))
      (node (ref "R86") (pin "2") (pinfunction "2_2") (pintype "passive"))
    )
    (net (code "56") (name "Net-(U2-VINA+)") (class "Default")
      (node (ref "R13") (pin "2") (pinfunction "2_2") (pintype "passive"))
      (node (ref "R14") (pin "2") (pinfunction "2_2") (pintype "passive"))
      (node (ref "U2") (pin "3") (pinfunction "VINA+_3") (pintype "passive"))
    )
    (net (code "57") (name "Net-(U2-VINA-)") (class "Default")
      (node (ref "R11") (pin "2") (pinfunction "2_2") (pintype "passive"))
      (node (ref "R12") (pin "2") (pinfunction "2_2") (pintype "passive"))
      (node (ref "U2") (pin "2") (pinfunction "VINA-_2") (pintype "passive"))
    )
    (net (code "58") (name "Net-(U2-VINB+)") (class "Default")
      (node (ref "R18") (pin "2") (pinfunction "2_2") (pintype "passive"))
      (node (ref "R19") (pin "2") (pinfunction "2_2") (pintype "passive"))
      (node (ref "U2") (pin "5") (pinfunction "VINB+_5") (pintype "passive"))
    )
    (net (code "59") (name "Net-(U2-VINB-)") (class "Default")
      (node (ref "C6") (pin "1") (pinfunction "1_1") (pintype "passive"))
      (node (ref "R16") (pin "2") (pinfunction "2_2") (pintype "passive"))
      (node (ref "R17") (pin "2") (pinfunction "2_2") (pintype "passive"))
      (node (ref "U2") (pin "6") (pinfunction "VINB-_6") (pintype "passive"))
    )
    (net (code "60") (name "Net-(U2-VOUTA)") (class "Default")
      (node (ref "R12") (pin "1") (pinfunction "1_1") (pintype "passive"))
      (node (ref "R16") (pin "1") (pinfunction "1_1") (pintype "passive"))
      (node (ref "U2") (pin "1") (pinfunction "VOUTA_1") (pintype "passive"))
    )
    (net (code "61") (name "Net-(U5-VINA+)") (class "Default")
      (node (ref "R4") (pin "2") (pinfunction "2_2") (pintype "passive"))
      (node (ref "R5") (pin "2") (pinfunction "2_2") (pintype "passive"))
      (node (ref "U5") (pin "3") (pinfunction "VINA+_3") (pintype "passive"))
    )
    (net (code "62") (name "Net-(U5-VINA-)") (class "Default")
      (node (ref "R2") (pin "2") (pinfunction "2_2") (pintype "passive"))
      (node (ref "R3") (pin "2") (pinfunction "2_2") (pintype "passive"))
      (node (ref "U5") (pin "2") (pinfunction "VINA-_2") (pintype "passive"))
    )
    (net (code "63") (name "Net-(U5-VINB+)") (class "Default")
      (node (ref "R10") (pin "2") (pinfunction "2_2") (pintype "passive"))
      (node (ref "R9") (pin "2") (pinfunction "2_2") (pintype "passive"))
      (node (ref "U5") (pin "5") (pinfunction "VINB+_5") (pintype "passive"))
    )
    (net (code "64") (name "Net-(U5-VINB-)") (class "Default")
      (node (ref "C4") (pin "1") (pinfunction "1_1") (pintype "passive"))
      (node (ref "R7") (pin "2") (pinfunction "2_2") (pintype "passive"))
      (node (ref "R8") (pin "2") (pinfunction "2_2") (pintype "passive"))
      (node (ref "U5") (pin "6") (pinfunction "VINB-_6") (pintype "passive"))
    )
    (net (code "65") (name "Net-(U5-VOUTA)") (class "Default")
      (node (ref "R3") (pin "1") (pinfunction "1_1") (pintype "passive"))
      (node (ref "R7") (pin "1") (pinfunction "1_1") (pintype "passive"))
      (node (ref "U5") (pin "1") (pinfunction "VOUTA_1") (pintype "passive"))
    )
    (net (code "66") (name "Net-(U7-VINA+)") (class "Default")
      (node (ref "R66") (pin "2") (pinfunction "2_2") (pintype "passive"))
      (node (ref "R67") (pin "2") (pinfunction "2_2") (pintype "passive"))
      (node (ref "U7") (pin "3") (pinfunction "VINA+_3") (pintype "passive"))
    )
    (net (code "67") (name "Net-(U7-VINA-)") (class "Default")
      (node (ref "R20") (pin "2") (pinfunction "2_2") (pintype "passive"))
      (node (ref "R21") (pin "2") (pinfunction "2_2") (pintype "passive"))
      (node (ref "U7") (pin "2") (pinfunction "VINA-_2") (pintype "passive"))
    )
    (net (code "68") (name "Net-(U7-VINB+)") (class "Default")
      (node (ref "R71") (pin "2") (pinfunction "2_2") (pintype "passive"))
      (node (ref "R72") (pin "2") (pinfunction "2_2") (pintype "passive"))
      (node (ref "U7") (pin "5") (pinfunction "VINB+_5") (pintype "passive"))
    )
    (net (code "69") (name "Net-(U7-VINB-)") (class "Default")
      (node (ref "C15") (pin "1") (pinfunction "1_1") (pintype "passive"))
      (node (ref "R69") (pin "2") (pinfunction "2_2") (pintype "passive"))
      (node (ref "R70") (pin "2") (pinfunction "2_2") (pintype "passive"))
      (node (ref "U7") (pin "6") (pinfunction "VINB-_6") (pintype "passive"))
    )
    (net (code "70") (name "Net-(U7-VOUTA)") (class "Default")
      (node (ref "R21") (pin "1") (pinfunction "1_1") (pintype "passive"))
      (node (ref "R69") (pin "1") (pinfunction "1_1") (pintype "passive"))
      (node (ref "U7") (pin "1") (pinfunction "VOUTA_1") (pintype "passive"))
    )
    (net (code "71") (name "Net-(U8-VINA+)") (class "Default")
      (node (ref "R75") (pin "2") (pinfunction "2_2") (pintype "passive"))
      (node (ref "R76") (pin "2") (pinfunction "2_2") (pintype "passive"))
      (node (ref "U8") (pin "3") (pinfunction "VINA+_3") (pintype "passive"))
    )
    (net (code "72") (name "Net-(U8-VINA-)") (class "Default")
      (node (ref "R73") (pin "2") (pinfunction "2_2") (pintype "passive"))
      (node (ref "R74") (pin "2") (pinfunction "2_2") (pintype "passive"))
      (node (ref "U8") (pin "2") (pinfunction "VINA-_2") (pintype "passive"))
    )
    (net (code "73") (name "Net-(U8-VINB+)") (class "Default")
      (node (ref "R80") (pin "2") (pinfunction "2_2") (pintype "passive"))
      (node (ref "R81") (pin "2") (pinfunction "2_2") (pintype "passive"))
      (node (ref "U8") (pin "5") (pinfunction "VINB+_5") (pintype "passive"))
    )
    (net (code "74") (name "Net-(U8-VINB-)") (class "Default")
      (node (ref "C17") (pin "1") (pinfunction "1_1") (pintype "passive"))
      (node (ref "R78") (pin "2") (pinfunction "2_2") (pintype "passive"))
      (node (ref "R79") (pin "2") (pinfunction "2_2") (pintype "passive"))
      (node (ref "U8") (pin "6") (pinfunction "VINB-_6") (pintype "passive"))
    )
    (net (code "75") (name "Net-(U8-VOUTA)") (class "Default")
      (node (ref "R74") (pin "1") (pinfunction "1_1") (pintype "passive"))
      (node (ref "R78") (pin "1") (pinfunction "1_1") (pintype "passive"))
      (node (ref "U8") (pin "1") (pinfunction "VOUTA_1") (pintype "passive"))
    )
    (net (code "76") (name "Net-(U9-VINA+)") (class "Default")
      (node (ref "R84") (pin "2") (pinfunction "2_2") (pintype "passive"))
      (node (ref "R85") (pin "2") (pinfunction "2_2") (pintype "passive"))
      (node (ref "U9") (pin "3") (pinfunction "VINA+_3") (pintype "passive"))
    )
    (net (code "77") (name "Net-(U9-VINA-)") (class "Default")
      (node (ref "R82") (pin "2") (pinfunction "2_2") (pintype "passive"))
      (node (ref "R83") (pin "2") (pinfunction "2_2") (pintype "passive"))
      (node (ref "U9") (pin "2") (pinfunction "VINA-_2") (pintype "passive"))
    )
    (net (code "78") (name "Net-(U9-VINB+)") (class "Default")
      (node (ref "R89") (pin "2") (pinfunction "2_2") (pintype "passive"))
      (node (ref "R90") (pin "2") (pinfunction "2_2") (pintype "passive"))
      (node (ref "U9") (pin "5") (pinfunction "VINB+_5") (pintype "passive"))
    )
    (net (code "79") (name "Net-(U9-VINB-)") (class "Default")
      (node (ref "C19") (pin "1") (pinfunction "1_1") (pintype "passive"))
      (node (ref "R87") (pin "2") (pinfunction "2_2") (pintype "passive"))
      (node (ref "R88") (pin "2") (pinfunction "2_2") (pintype "passive"))
      (node (ref "U9") (pin "6") (pinfunction "VINB-_6") (pintype "passive"))
    )
    (net (code "80") (name "Net-(U9-VOUTA)") (class "Default")
      (node (ref "R83") (pin "1") (pinfunction "1_1") (pintype "passive"))
      (node (ref "R87") (pin "1") (pinfunction "1_1") (pintype "passive"))
      (node (ref "U9") (pin "1") (pinfunction "VOUTA_1") (pintype "passive"))
    )
    (net (code "81") (name "O2") (class "Default")
      (node (ref "R73") (pin "1") (pinfunction "1_1") (pintype "passive"))
      (node (ref "TP25") (pin "TP") (pinfunction "TP_TP") (pintype "input"))
    )
    (net (code "82") (name "O2_FIL") (class "Default")
      (node (ref "C17") (pin "2") (pinfunction "2_2") (pintype "passive"))
      (node (ref "R79") (pin "1") (pinfunction "1_1") (pintype "passive"))
      (node (ref "TP26") (pin "TP") (pinfunction "TP_TP") (pintype "input"))
      (node (ref "U8") (pin "7") (pinfunction "VOUTB_7") (pintype "passive"))
    )
    (net (code "83") (name "REV_LIMIT_LED") (class "Default")
      (node (ref "R27") (pin "1") (pinfunction "1_1") (pintype "passive"))
      (node (ref "TP50") (pin "TP") (pinfunction "TP_TP") (pintype "input"))
    )
    (net (code "84") (name "SCK_3V3") (class "Default")
      (node (ref "J8") (pin "3") (pinfunction "3_3") (pintype "passive"))
      (node (ref "TP12") (pin "TP") (pinfunction "TP_TP") (pintype "input"))
      (node (ref "U1") (pin "3") (pinfunction "A2_3") (pintype "input"))
    )
    (net (code "85") (name "SCK_5V") (class "Default")
      (node (ref "TP37") (pin "TP") (pinfunction "TP_TP") (pintype "input"))
      (node (ref "U1") (pin "12") (pinfunction "B2_12") (pintype "output"))
    )
    (net (code "86") (name "SPARK") (class "Default")
      (node (ref "J2") (pin "1") (pinfunction "1_1") (pintype "passive"))
      (node (ref "Q7") (pin "1") (pinfunction "G_1") (pintype "passive"))
      (node (ref "TP18") (pin "TP") (pinfunction "TP_TP") (pintype "input"))
    )
    (net (code "87") (name "SPARK_LED") (class "Default")
      (node (ref "R22") (pin "1") (pinfunction "1_1") (pintype "passive"))
      (node (ref "TP48") (pin "TP") (pinfunction "TP_TP") (pintype "input"))
    )
    (net (code "88") (name "SPR_IN1") (class "Default")
      (node (ref "JP1") (pin "1") (pinfunction "1_1") (pintype "passive"))
    )
    (net (code "89") (name "SPR_IN2") (class "Default")
      (node (ref "JP2") (pin "1") (pinfunction "1_1") (pintype "passive"))
    )
    (net (code "90") (name "SPR_IN3") (class "Default")
      (node (ref "JP3") (pin "1") (pinfunction "1_1") (pintype "passive"))
    )
    (net (code "91") (name "TPS") (class "Default")
      (node (ref "R82") (pin "1") (pinfunction "1_1") (pintype "passive"))
      (node (ref "TP27") (pin "TP") (pinfunction "TP_TP") (pintype "input"))
    )
    (net (code "92") (name "TPS_FIL") (class "Default")
      (node (ref "C19") (pin "2") (pinfunction "2_2") (pintype "passive"))
      (node (ref "R88") (pin "1") (pinfunction "1_1") (pintype "passive"))
      (node (ref "TP28") (pin "TP") (pinfunction "TP_TP") (pintype "input"))
      (node (ref "U9") (pin "7") (pinfunction "VOUTB_7") (pintype "passive"))
    )
    (net (code "93") (name "unconnected-(J1-Pad1)") (class "Default")
      (node (ref "J1") (pin "1") (pinfunction "1_1") (pintype "passive"))
    )
    (net (code "94") (name "unconnected-(J1-Pad2)") (class "Default")
      (node (ref "J1") (pin "2") (pinfunction "2_2") (pintype "passive"))
    )
    (net (code "95") (name "unconnected-(J1-Pad3)") (class "Default")
      (node (ref "J1") (pin "3") (pinfunction "3_3") (pintype "passive"))
    )
    (net (code "96") (name "unconnected-(J1-Pad5)") (class "Default")
      (node (ref "J1") (pin "5") (pinfunction "5_5") (pintype "passive"))
    )
    (net (code "97") (name "unconnected-(J1-Pad6)") (class "Default")
      (node (ref "J1") (pin "6") (pinfunction "6_6") (pintype "passive"))
    )
    (net (code "98") (name "unconnected-(J1-Pad7)") (class "Default")
      (node (ref "J1") (pin "7") (pinfunction "7_7") (pintype "passive"))
    )
    (net (code "99") (name "unconnected-(J1-Pad8)") (class "Default")
      (node (ref "J1") (pin "8") (pinfunction "8_8") (pintype "passive"))
    )
    (net (code "100") (name "unconnected-(J1-Pad9)") (class "Default")
      (node (ref "J1") (pin "9") (pinfunction "9_9") (pintype "passive"))
    )
    (net (code "101") (name "unconnected-(J2-Pad2)") (class "Default")
      (node (ref "J2") (pin "2") (pinfunction "2_2") (pintype "passive"))
    )
    (net (code "102") (name "unconnected-(J2-Pad5)") (class "Default")
      (node (ref "J2") (pin "5") (pinfunction "5_5") (pintype "passive"))
    )
    (net (code "103") (name "unconnected-(J2-Pad6)") (class "Default")
      (node (ref "J2") (pin "6") (pinfunction "6_6") (pintype "passive"))
    )
    (net (code "104") (name "unconnected-(J2-Pad7)") (class "Default")
      (node (ref "J2") (pin "7") (pinfunction "7_7") (pintype "passive"))
    )
    (net (code "105") (name "unconnected-(J2-Pad8)") (class "Default")
      (node (ref "J2") (pin "8") (pinfunction "8_8") (pintype "passive"))
    )
    (net (code "106") (name "unconnected-(J3-Pad1)") (class "Default")
      (node (ref "J3") (pin "1") (pinfunction "1_1") (pintype "passive"))
    )
    (net (code "107") (name "unconnected-(J3-Pad2)") (class "Default")
      (node (ref "J3") (pin "2") (pinfunction "2_2") (pintype "passive"))
    )
    (net (code "108") (name "unconnected-(J3-Pad3)") (class "Default")
      (node (ref "J3") (pin "3") (pinfunction "3_3") (pintype "passive"))
    )
    (net (code "109") (name "unconnected-(J3-Pad4)") (class "Default")
      (node (ref "J3") (pin "4") (pinfunction "4_4") (pintype "passive"))
    )
    (net (code "110") (name "unconnected-(J3-Pad5)") (class "Default")
      (node (ref "J3") (pin "5") (pinfunction "5_5") (pintype "passive"))
    )
    (net (code "111") (name "unconnected-(J3-Pad6)") (class "Default")
      (node (ref "J3") (pin "6") (pinfunction "6_6") (pintype "passive"))
    )
    (net (code "112") (name "unconnected-(J3-Pad7)") (class "Default")
      (node (ref "J3") (pin "7") (pinfunction "7_7") (pintype "passive"))
    )
    (net (code "113") (name "unconnected-(J3-Pad8)") (class "Default")
      (node (ref "J3") (pin "8") (pinfunction "8_8") (pintype "passive"))
    )
    (net (code "114") (name "unconnected-(J4-Pad1)") (class "Default")
      (node (ref "J4") (pin "1") (pinfunction "1_1") (pintype "passive"))
    )
    (net (code "115") (name "unconnected-(J4-Pad3)") (class "Default")
      (node (ref "J4") (pin "3") (pinfunction "3_3") (pintype "passive"))
    )
    (net (code "116") (name "unconnected-(J5-Pad1)") (class "Default")
      (node (ref "J5") (pin "1") (pinfunction "1_1") (pintype "passive"))
    )
    (net (code "117") (name "unconnected-(J5-Pad2)") (class "Default")
      (node (ref "J5") (pin "2") (pinfunction "2_2") (pintype "passive"))
    )
    (net (code "118") (name "unconnected-(J5-Pad3)") (class "Default")
      (node (ref "J5") (pin "3") (pinfunction "3_3") (pintype "passive"))
    )
    (net (code "119") (name "unconnected-(J5-Pad4)") (class "Default")
      (node (ref "J5") (pin "4") (pinfunction "4_4") (pintype "passive"))
    )
    (net (code "120") (name "unconnected-(J5-Pad5)") (class "Default")
      (node (ref "J5") (pin "5") (pinfunction "5_5") (pintype "passive"))
    )
    (net (code "121") (name "unconnected-(J5-Pad6)") (class "Default")
      (node (ref "J5") (pin "6") (pinfunction "6_6") (pintype "passive"))
    )
    (net (code "122") (name "unconnected-(J5-Pad7)") (class "Default")
      (node (ref "J5") (pin "7") (pinfunction "7_7") (pintype "passive"))
    )
    (net (code "123") (name "unconnected-(J5-Pad8)") (class "Default")
      (node (ref "J5") (pin "8") (pinfunction "8_8") (pintype "passive"))
    )
    (net (code "124") (name "unconnected-(J6-Pad1)") (class "Default")
      (node (ref "J6") (pin "1") (pinfunction "1_1") (pintype "passive"))
    )
    (net (code "125") (name "unconnected-(J6-Pad2)") (class "Default")
      (node (ref "J6") (pin "2") (pinfunction "2_2") (pintype "passive"))
    )
    (net (code "126") (name "unconnected-(J6-Pad3)") (class "Default")
      (node (ref "J6") (pin "3") (pinfunction "3_3") (pintype "passive"))
    )
    (net (code "127") (name "unconnected-(J6-Pad4)") (class "Default")
      (node (ref "J6") (pin "4") (pinfunction "4_4") (pintype "passive"))
    )
    (net (code "128") (name "unconnected-(J6-Pad5)") (class "Default")
      (node (ref "J6") (pin "5") (pinfunction "5_5") (pintype "passive"))
    )
    (net (code "129") (name "unconnected-(J6-Pad6)") (class "Default")
      (node (ref "J6") (pin "6") (pinfunction "6_6") (pintype "passive"))
    )
    (net (code "130") (name "unconnected-(J7-Pad1)") (class "Default")
      (node (ref "J7") (pin "1") (pinfunction "1_1") (pintype "bidirectional"))
    )
    (net (code "131") (name "unconnected-(J7-Pad2)") (class "Default")
      (node (ref "J7") (pin "2") (pinfunction "2_2") (pintype "bidirectional"))
    )
    (net (code "132") (name "unconnected-(J7-Pad3)") (class "Default")
      (node (ref "J7") (pin "3") (pinfunction "3_3") (pintype "bidirectional"))
    )
    (net (code "133") (name "unconnected-(J7-Pad4)") (class "Default")
      (node (ref "J7") (pin "4") (pinfunction "4_4") (pintype "bidirectional"))
    )
    (net (code "134") (name "unconnected-(J7-Pad5)") (class "Default")
      (node (ref "J7") (pin "5") (pinfunction "5_5") (pintype "bidirectional"))
    )
    (net (code "135") (name "unconnected-(J7-Pad6)") (class "Default")
      (node (ref "J7") (pin "6") (pinfunction "6_6") (pintype "bidirectional"))
    )
    (net (code "136") (name "unconnected-(J7-Pad7)") (class "Default")
      (node (ref "J7") (pin "7") (pinfunction "7_7") (pintype "bidirectional"))
    )
    (net (code "137") (name "unconnected-(J7-Pad8)") (class "Default")
      (node (ref "J7") (pin "8") (pinfunction "8_8") (pintype "bidirectional"))
    )
    (net (code "138") (name "unconnected-(J7-Pad9)") (class "Default")
      (node (ref "J7") (pin "9") (pinfunction "9_9") (pintype "bidirectional"))
    )
    (net (code "139") (name "unconnected-(J7-Pad10)") (class "Default")
      (node (ref "J7") (pin "10") (pinfunction "10_10") (pintype "bidirectional"))
    )
    (net (code "140") (name "unconnected-(J7-Pad11)") (class "Default")
      (node (ref "J7") (pin "11") (pinfunction "11_11") (pintype "bidirectional"))
    )
    (net (code "141") (name "unconnected-(J7-Pad12)") (class "Default")
      (node (ref "J7") (pin "12") (pinfunction "12_12") (pintype "bidirectional"))
    )
    (net (code "142") (name "unconnected-(J7-Pad13)") (class "Default")
      (node (ref "J7") (pin "13") (pinfunction "13_13") (pintype "bidirectional"))
    )
    (net (code "143") (name "unconnected-(J7-Pad14)") (class "Default")
      (node (ref "J7") (pin "14") (pinfunction "14_14") (pintype "bidirectional"))
    )
    (net (code "144") (name "unconnected-(J7-Pad15)") (class "Default")
      (node (ref "J7") (pin "15") (pinfunction "15_15") (pintype "bidirectional"))
    )
    (net (code "145") (name "unconnected-(J7-Pad16)") (class "Default")
      (node (ref "J7") (pin "16") (pinfunction "16_16") (pintype "bidirectional"))
    )
    (net (code "146") (name "unconnected-(J7-Pad17)") (class "Default")
      (node (ref "J7") (pin "17") (pinfunction "17_17") (pintype "bidirectional"))
    )
    (net (code "147") (name "unconnected-(J7-Pad18)") (class "Default")
      (node (ref "J7") (pin "18") (pinfunction "18_18") (pintype "bidirectional"))
    )
    (net (code "148") (name "unconnected-(J7-Pad19)") (class "Default")
      (node (ref "J7") (pin "19") (pinfunction "19_19") (pintype "bidirectional"))
    )
    (net (code "149") (name "unconnected-(J7-Pad20)") (class "Default")
      (node (ref "J7") (pin "20") (pinfunction "20_20") (pintype "bidirectional"))
    )
    (net (code "150") (name "unconnected-(J7-Pad21)") (class "Default")
      (node (ref "J7") (pin "21") (pinfunction "21_21") (pintype "bidirectional"))
    )
    (net (code "151") (name "unconnected-(J7-Pad22)") (class "Default")
      (node (ref "J7") (pin "22") (pinfunction "22_22") (pintype "bidirectional"))
    )
    (net (code "152") (name "unconnected-(J7-Pad23)") (class "Default")
      (node (ref "J7") (pin "23") (pinfunction "23_23") (pintype "bidirectional"))
    )
    (net (code "153") (name "unconnected-(J8-Pad5)") (class "Default")
      (node (ref "J8") (pin "5") (pinfunction "5_5") (pintype "passive"))
    )
    (net (code "154") (name "unconnected-(J9-Pad3)") (class "Default")
      (node (ref "J9") (pin "3") (pinfunction "3_3") (pintype "passive"))
    )
    (net (code "155") (name "unconnected-(J9-Pad6)") (class "Default")
      (node (ref "J9") (pin "6") (pinfunction "6_6") (pintype "passive"))
    )
    (net (code "156") (name "unconnected-(J10-Pad3)") (class "Default")
      (node (ref "J10") (pin "3") (pinfunction "3_3") (pintype "passive"))
    )
    (net (code "157") (name "unconnected-(J10-Pad6)") (class "Default")
      (node (ref "J10") (pin "6") (pinfunction "6_6") (pintype "passive"))
    )
    (net (code "158") (name "unconnected-(U1-NC-Pad9)") (class "Default")
      (node (ref "U1") (pin "9") (pinfunction "NC_9") (pintype "no_connect"))
    )
    (net (code "159") (name "unconnected-(U1-NC_2-Pad6)") (class "Default")
      (node (ref "U1") (pin "6") (pinfunction "NC_2_6") (pintype "no_connect"))
    )
    (net (code "160") (name "unconnected-(U10-VREF-Pad5)") (class "Default")
      (node (ref "U10") (pin "5") (pinfunction "VREF_5") (pintype "output"))
    )
  )
)
